# Spectre-SCH_SH2__rev.net
KiCad netlist of a schematic drawn in Altium Designer
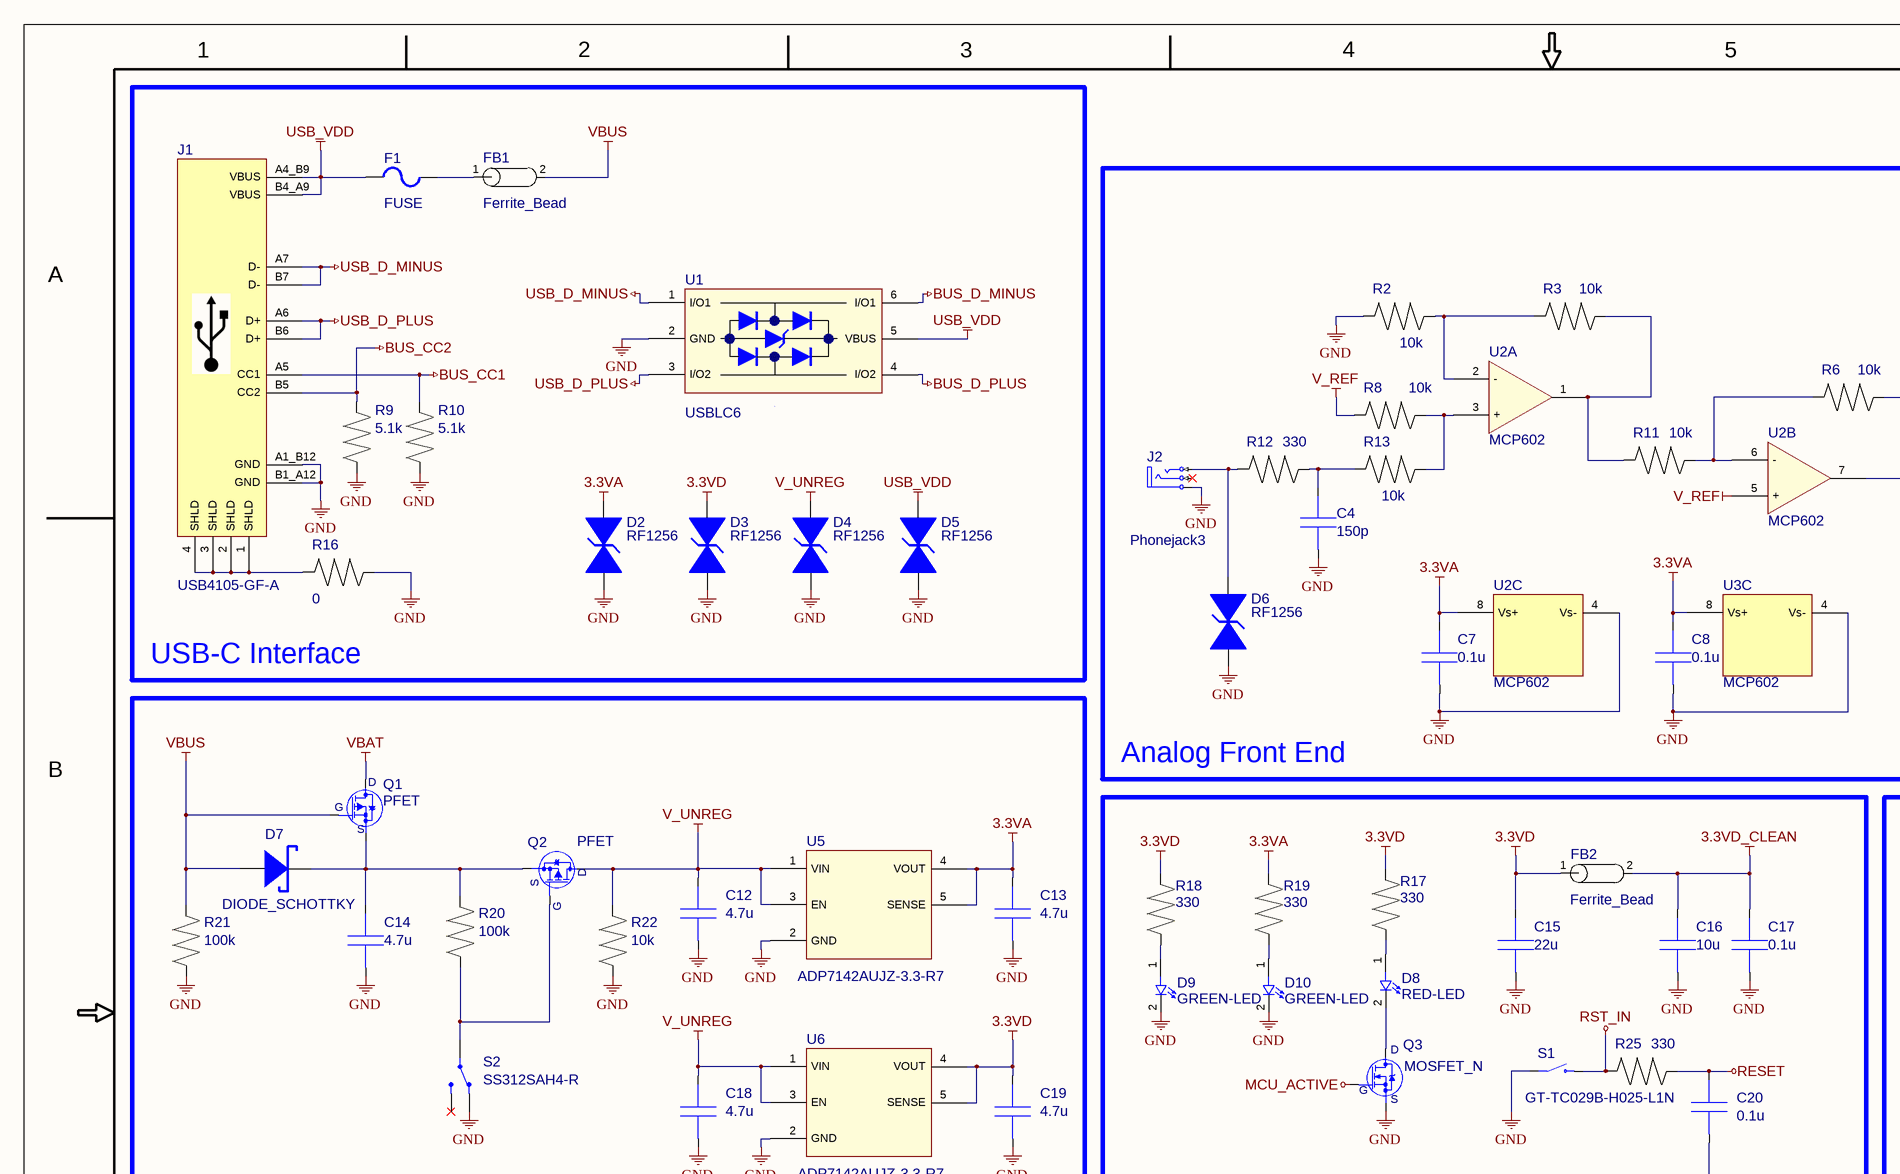
[diagram p0: Spectre-SCH_SH2_(rev).SchDoc, top left]
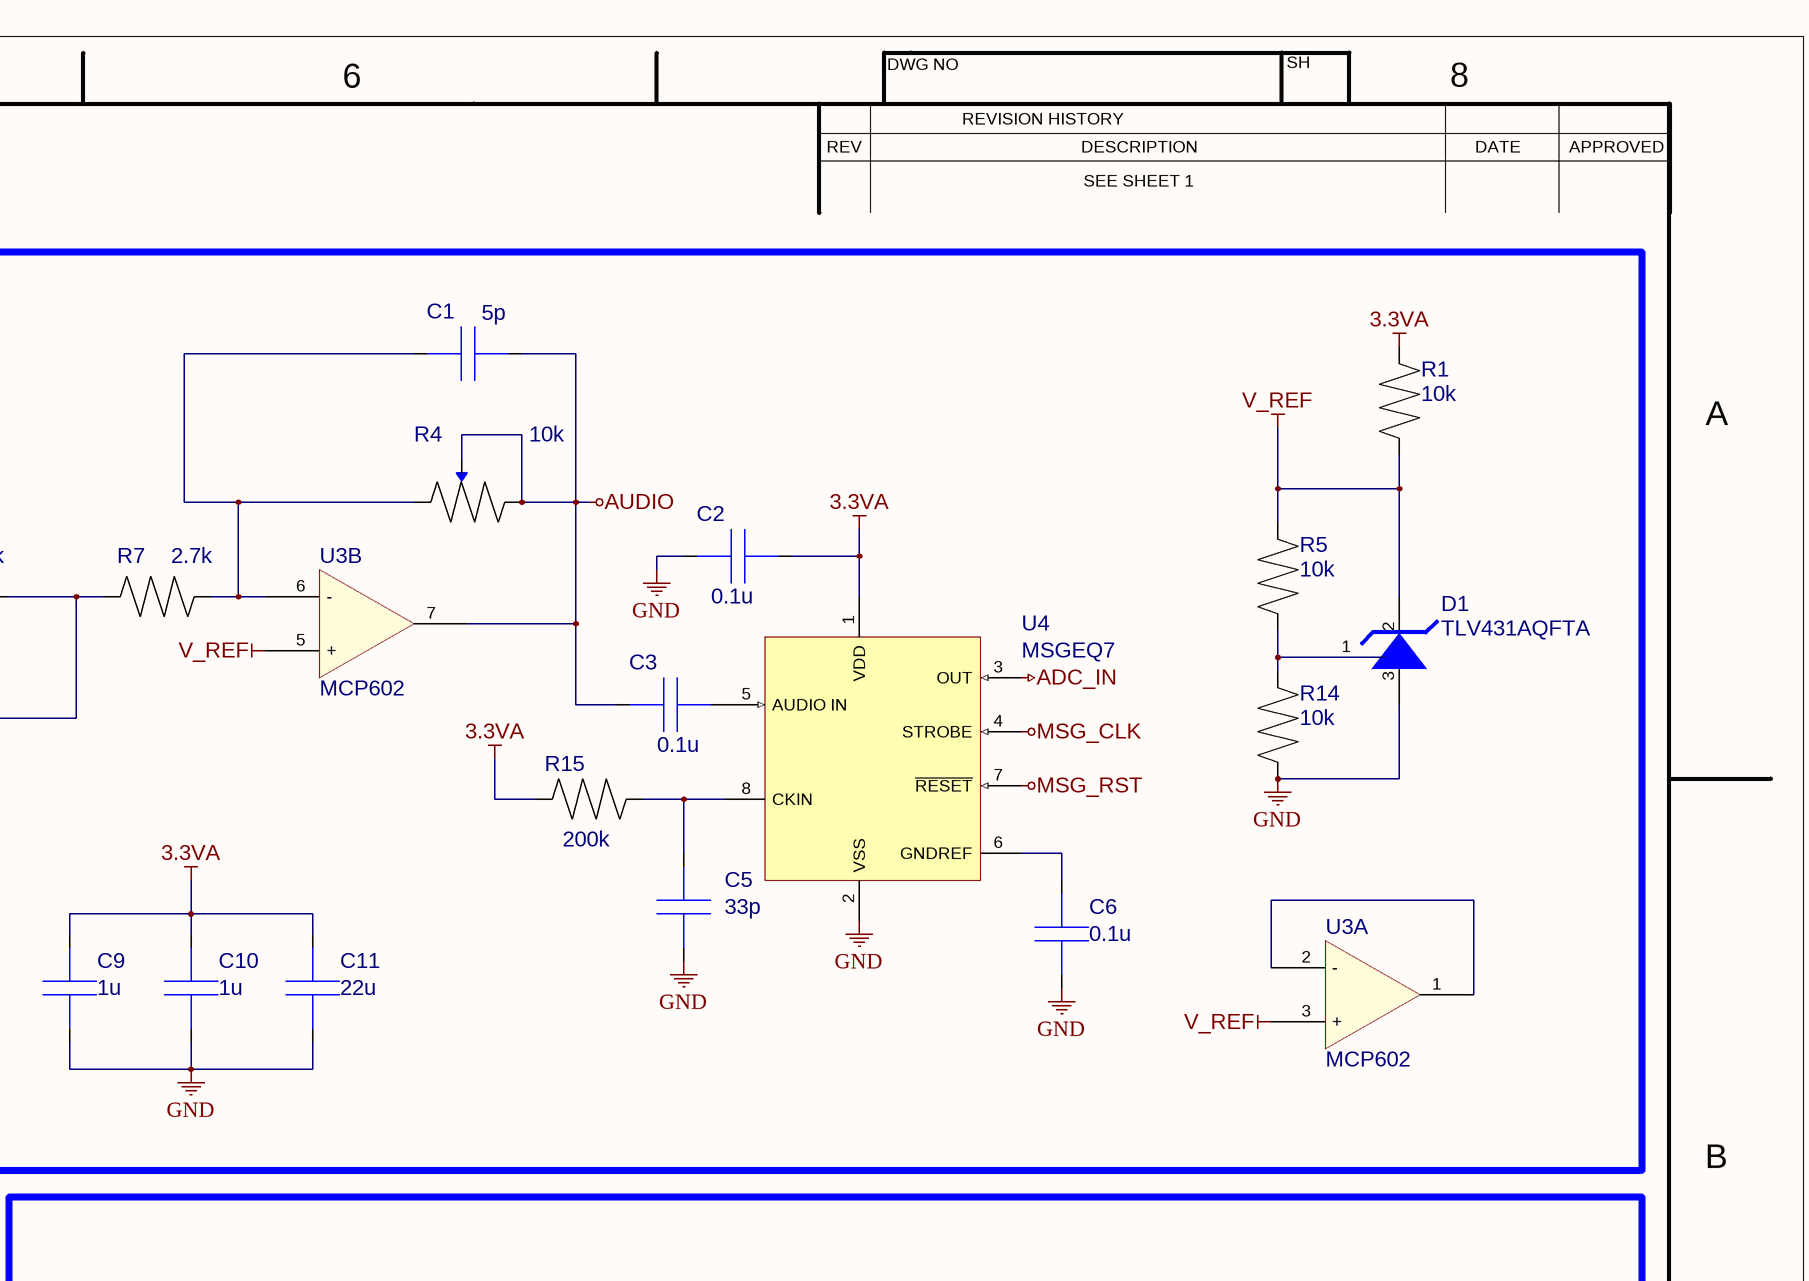
[diagram p1: Spectre-SCH_SH2_(rev).SchDoc, top right]
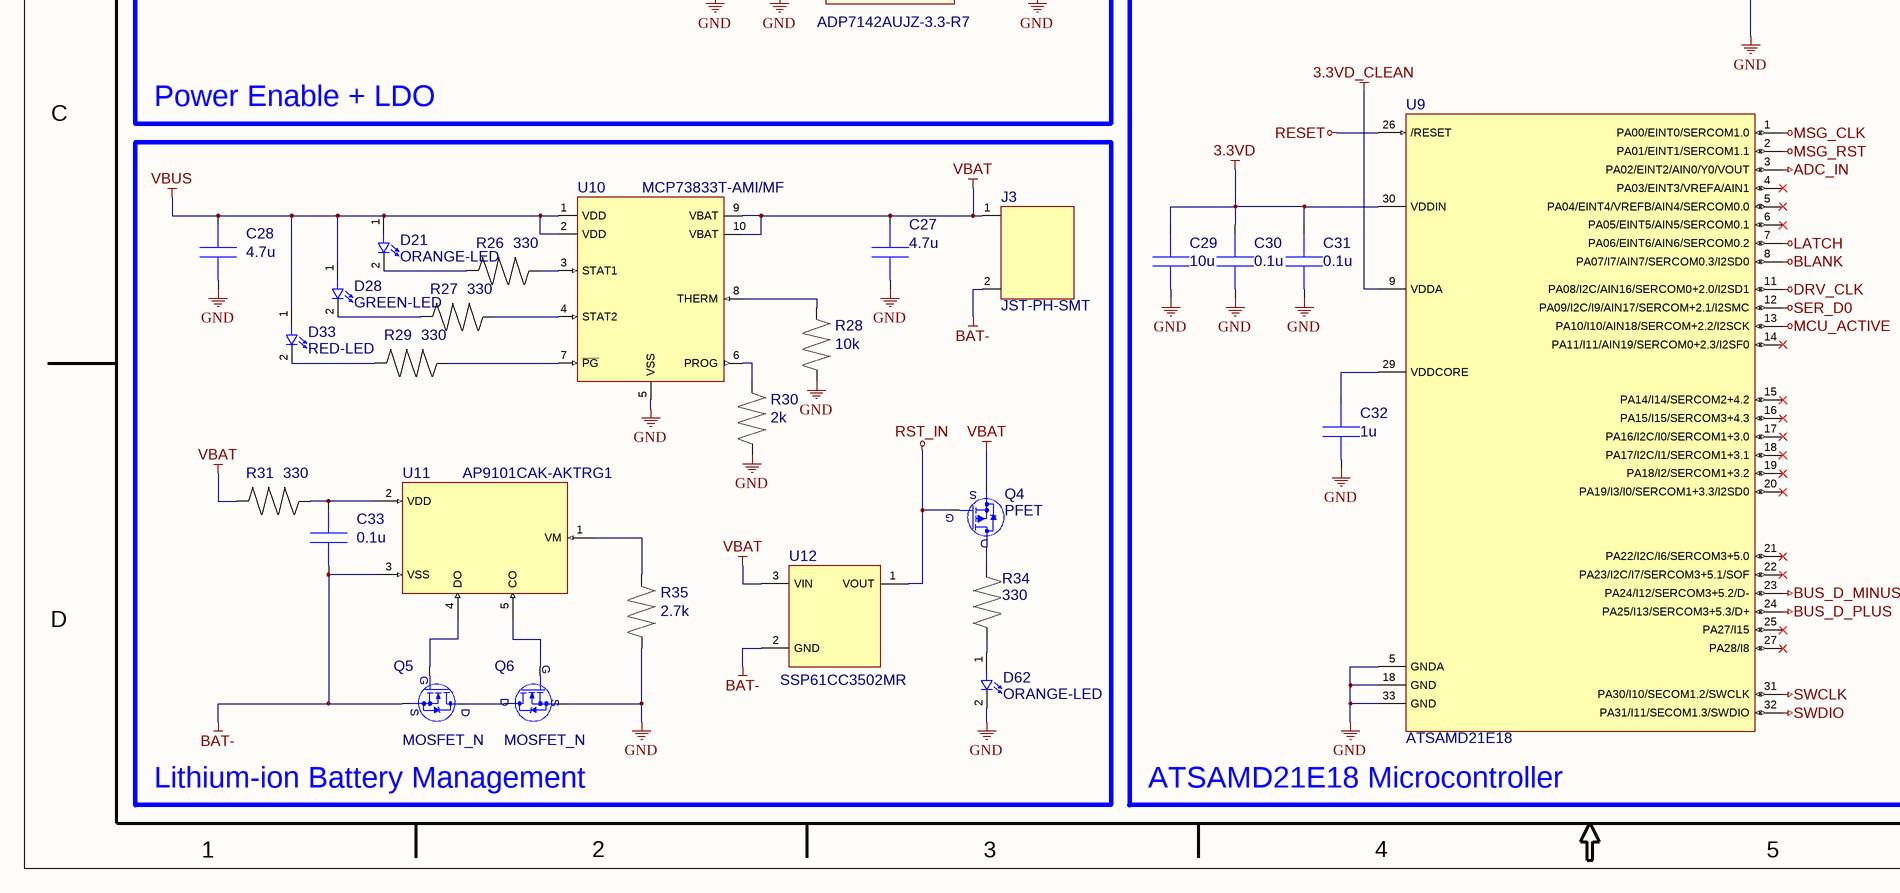
[diagram p2: Spectre-SCH_SH2_(rev).SchDoc, bottom left]
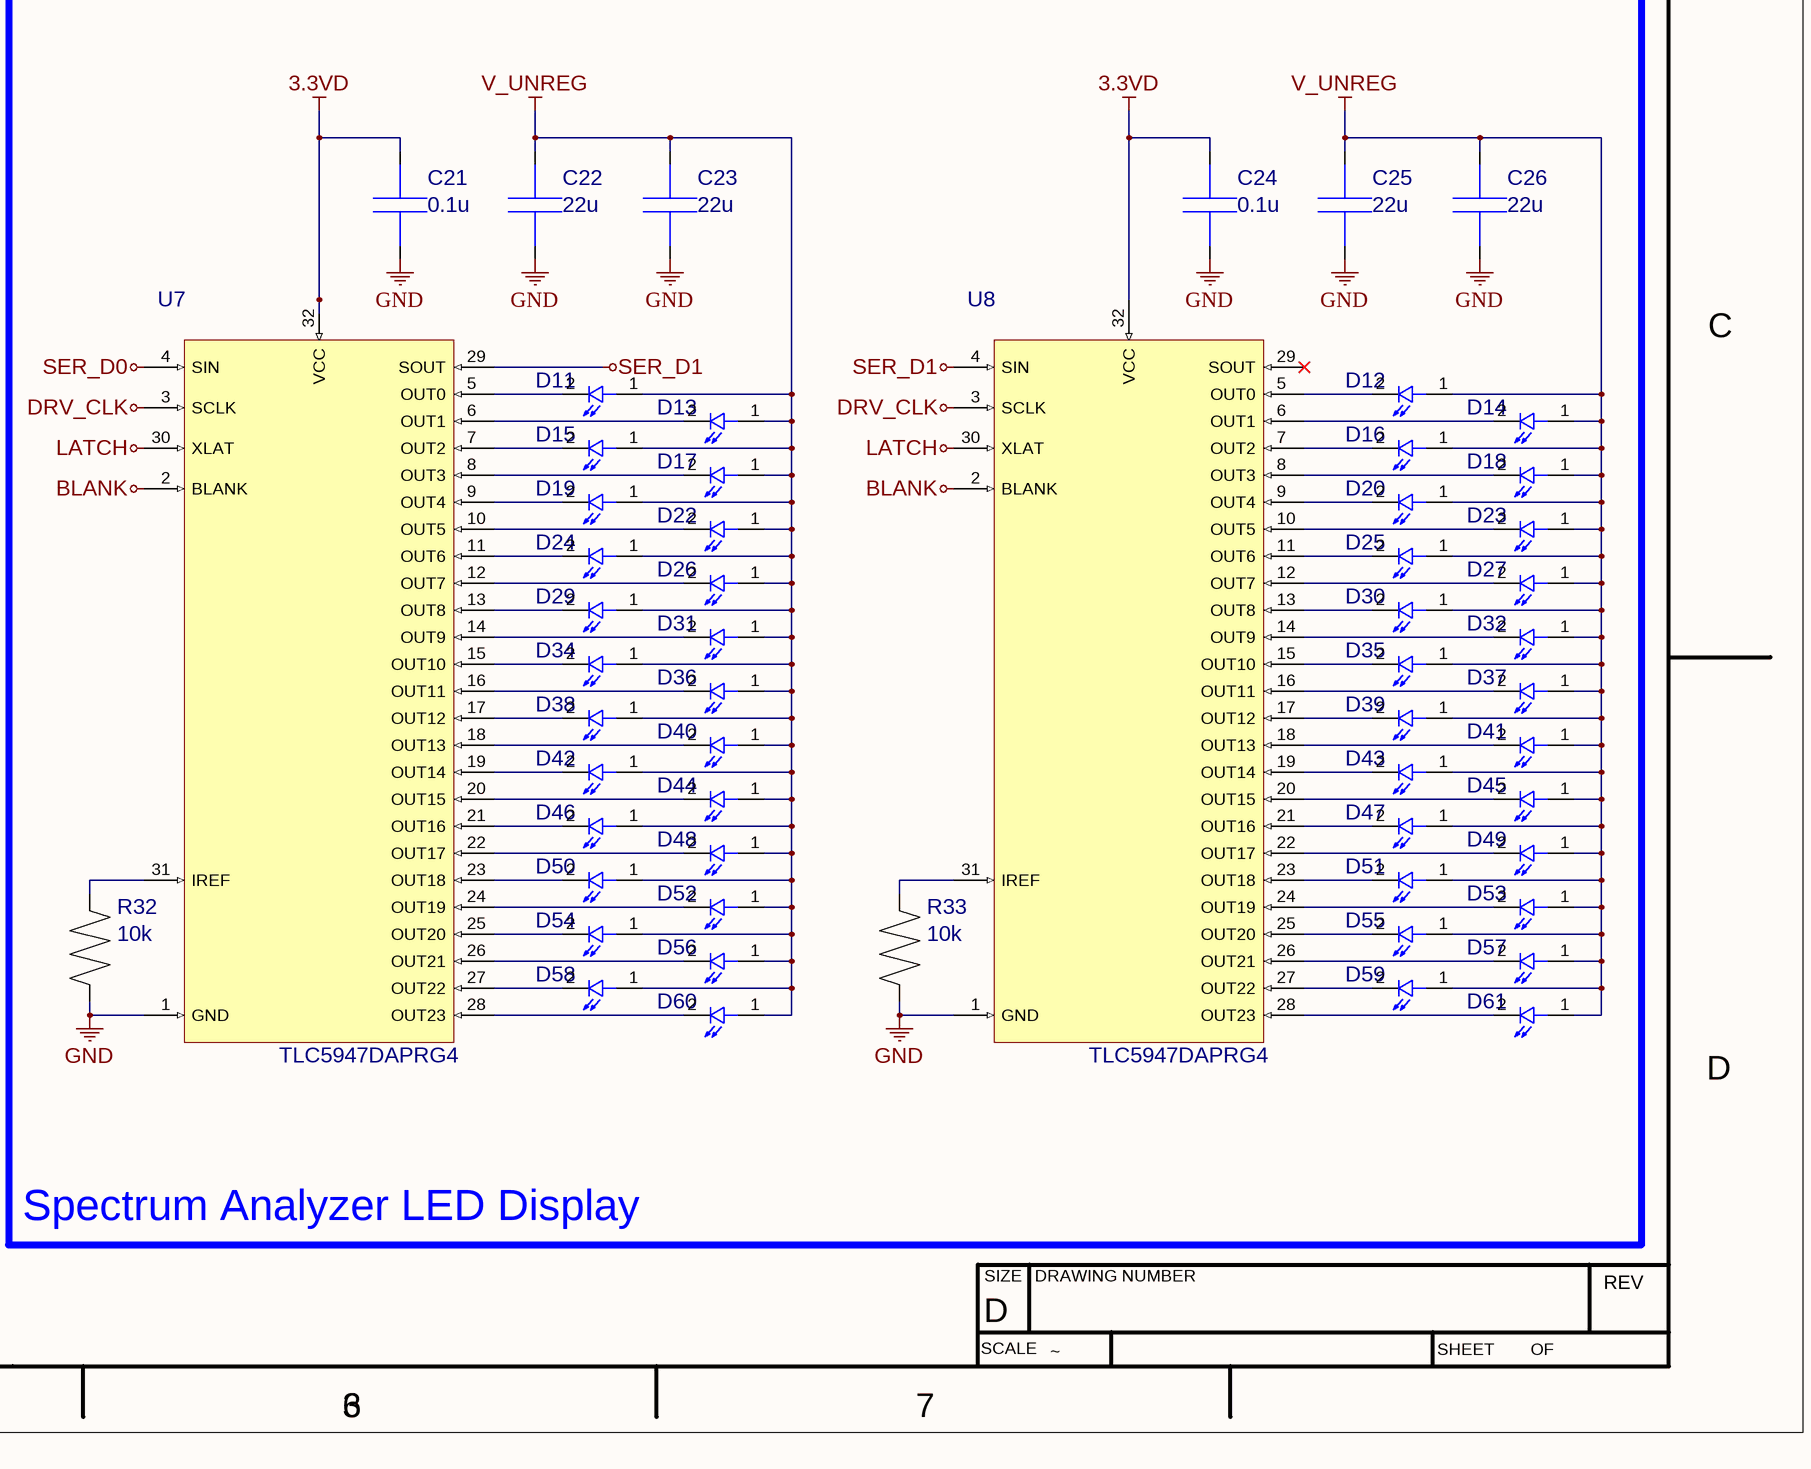
[diagram p3: Spectre-SCH_SH2_(rev).SchDoc, bottom right]

(export (version "E")
  (design (tool "Eeschema 10.0.6"))
  (components
    (comp (ref "C1") (value "5p") (footprint "0603") (libsource (lib "CAPACITORS") (part "CAP")))
    (comp (ref "C2") (value "0.1u") (footprint "0603") (libsource (lib "CAPACITORS") (part "CAP")))
    (comp (ref "C3") (value "0.1u") (footprint "0603") (libsource (lib "CAPACITORS") (part "CAP")))
    (comp (ref "C4") (value "150p") (footprint "0603") (libsource (lib "CAPACITORS") (part "CAP")))
    (comp (ref "C5") (value "33p") (footprint "0603") (libsource (lib "CAPACITORS") (part "CAP")))
    (comp (ref "C6") (value "0.1u") (footprint "0603") (libsource (lib "CAPACITORS") (part "CAP")))
    (comp (ref "C7") (value "0.1u") (footprint "0603") (libsource (lib "CAPACITORS") (part "CAP")))
    (comp (ref "C8") (value "0.1u") (footprint "0603") (libsource (lib "CAPACITORS") (part "CAP")))
    (comp (ref "C9") (value "1u") (footprint "0603") (libsource (lib "CAPACITORS") (part "CAP")))
    (comp (ref "C10") (value "1u") (footprint "0603") (libsource (lib "CAPACITORS") (part "CAP")))
    (comp (ref "C11") (value "22u") (footprint "0603") (libsource (lib "CAPACITORS") (part "CAP")))
    (comp (ref "C12") (value "4.7u") (footprint "0603") (libsource (lib "CAPACITORS") (part "CAP")))
    (comp (ref "C13") (value "4.7u") (footprint "0603") (libsource (lib "CAPACITORS") (part "CAP")))
    (comp (ref "C14") (value "4.7u") (footprint "0603") (libsource (lib "CAPACITORS") (part "CAP")))
    (comp (ref "C15") (value "22u") (footprint "0603") (libsource (lib "CAPACITORS") (part "CAP")))
    (comp (ref "C16") (value "10u") (footprint "0603") (libsource (lib "CAPACITORS") (part "CAP")))
    (comp (ref "C17") (value "0.1u") (footprint "0603") (libsource (lib "CAPACITORS") (part "CAP")))
    (comp (ref "C18") (value "4.7u") (footprint "0603") (libsource (lib "CAPACITORS") (part "CAP")))
    (comp (ref "C19") (value "4.7u") (footprint "0603") (libsource (lib "CAPACITORS") (part "CAP")))
    (comp (ref "C20") (value "0.1u") (footprint "0603") (libsource (lib "CAPACITORS") (part "CAP")))
    (comp (ref "C21") (value "0.1u") (footprint "0603") (libsource (lib "CAPACITORS") (part "CAP")))
    (comp (ref "C22") (value "22u") (footprint "0603") (libsource (lib "CAPACITORS") (part "CAP")))
    (comp (ref "C23") (value "22u") (footprint "0603") (libsource (lib "CAPACITORS") (part "CAP")))
    (comp (ref "C24") (value "0.1u") (footprint "0603") (libsource (lib "CAPACITORS") (part "CAP")))
    (comp (ref "C25") (value "22u") (footprint "0603") (libsource (lib "CAPACITORS") (part "CAP")))
    (comp (ref "C26") (value "22u") (footprint "0603") (libsource (lib "CAPACITORS") (part "CAP")))
    (comp (ref "C27") (value "4.7u") (footprint "0603") (libsource (lib "CAPACITORS") (part "CAP")))
    (comp (ref "C28") (value "4.7u") (footprint "0603") (libsource (lib "CAPACITORS") (part "CAP")))
    (comp (ref "C29") (value "10u") (footprint "0603") (libsource (lib "CAPACITORS") (part "CAP")))
    (comp (ref "C30") (value "0.1u") (footprint "0603") (libsource (lib "CAPACITORS") (part "CAP")))
    (comp (ref "C31") (value "0.1u") (footprint "0603") (libsource (lib "CAPACITORS") (part "CAP")))
    (comp (ref "C32") (value "1u") (footprint "0603") (libsource (lib "CAPACITORS") (part "CAP")))
    (comp (ref "C33") (value "0.1u") (footprint "0603") (libsource (lib "CAPACITORS") (part "CAP")))
    (comp (ref "D1")
      (value "TLV431AQFTA")
      (footprint "SOT-23-3")
      (description "Shunt Voltage Reference IC Adjustable 1.24V 18 VV ±1% 15 mA SOT-23-3")
      (fields (field (name "MANUFACTURER") "Diodes Incorporated"))
      (libsource (lib "TLV431AQFTA") (part "TLV431AQFTA"))
    )
    (comp (ref "D2")
      (value "RF1256")
      (footprint "0603")
      (description "TVS DIODE BIDIR")
      (libsource (lib "SEMICONDUCTORS") (part "DIODE_TVS_BIDIR"))
    )
    (comp (ref "D3")
      (value "RF1256")
      (footprint "0603")
      (description "TVS DIODE BIDIR")
      (libsource (lib "SEMICONDUCTORS") (part "DIODE_TVS_BIDIR"))
    )
    (comp (ref "D4")
      (value "RF1256")
      (footprint "0603")
      (description "TVS DIODE BIDIR")
      (libsource (lib "SEMICONDUCTORS") (part "DIODE_TVS_BIDIR"))
    )
    (comp (ref "D5")
      (value "RF1256")
      (footprint "0603")
      (description "TVS DIODE BIDIR")
      (libsource (lib "SEMICONDUCTORS") (part "DIODE_TVS_BIDIR"))
    )
    (comp (ref "D6")
      (value "RF1256")
      (footprint "0603")
      (description "TVS DIODE BIDIR")
      (libsource (lib "SEMICONDUCTORS") (part "DIODE_TVS_BIDIR"))
    )
    (comp (ref "D7")
      (value "DIODE_SCHOTTKY")
      (footprint "SMA")
      (description "DIODE SCHOTTKY")
      (libsource (lib "SEMICONDUCTORS") (part "DIODE_SCHOTTKY"))
    )
    (comp (ref "D8") (value "RED-LED") (footprint "0603 LED") (libsource (lib "SMT-LED") (part "SMT-LED")))
    (comp (ref "D9") (value "GREEN-LED") (footprint "0603 LED") (libsource (lib "SMT-LED") (part "SMT-LED")))
    (comp (ref "D10") (value "GREEN-LED") (footprint "0603 LED") (libsource (lib "SMT-LED") (part "SMT-LED")))
    (comp (ref "D11") (value "RED-LED") (footprint "0603 LED") (libsource (lib "SMT-LED") (part "SMT-LED")))
    (comp (ref "D12") (value "RED-LED") (footprint "0603 LED") (libsource (lib "SMT-LED") (part "SMT-LED")))
    (comp (ref "D13")
      (value "ORANGE-LED")
      (footprint "0603 LED")
      (libsource (lib "SMT-LED") (part "SMT-LED"))
    )
    (comp (ref "D14")
      (value "ORANGE-LED")
      (footprint "0603 LED")
      (libsource (lib "SMT-LED") (part "SMT-LED"))
    )
    (comp (ref "D15")
      (value "YELLOW-LED")
      (footprint "0603 LED")
      (libsource (lib "SMT-LED") (part "SMT-LED"))
    )
    (comp (ref "D16")
      (value "YELLOW-LED")
      (footprint "0603 LED")
      (libsource (lib "SMT-LED") (part "SMT-LED"))
    )
    (comp (ref "D17")
      (value "YELLOW-LED")
      (footprint "0603 LED")
      (libsource (lib "SMT-LED") (part "SMT-LED"))
    )
    (comp (ref "D18")
      (value "YELLOW-LED")
      (footprint "0603 LED")
      (libsource (lib "SMT-LED") (part "SMT-LED"))
    )
    (comp (ref "D19") (value "GREEN-LED") (footprint "0603 LED") (libsource (lib "SMT-LED") (part "SMT-LED")))
    (comp (ref "D20") (value "GREEN-LED") (footprint "0603 LED") (libsource (lib "SMT-LED") (part "SMT-LED")))
    (comp (ref "D21")
      (value "ORANGE-LED")
      (footprint "0603 LED")
      (libsource (lib "SMT-LED") (part "SMT-LED"))
    )
    (comp (ref "D22") (value "GREEN-LED") (footprint "0603 LED") (libsource (lib "SMT-LED") (part "SMT-LED")))
    (comp (ref "D23") (value "GREEN-LED") (footprint "0603 LED") (libsource (lib "SMT-LED") (part "SMT-LED")))
    (comp (ref "D24") (value "RED-LED") (footprint "0603 LED") (libsource (lib "SMT-LED") (part "SMT-LED")))
    (comp (ref "D25") (value "RED-LED") (footprint "0603 LED") (libsource (lib "SMT-LED") (part "SMT-LED")))
    (comp (ref "D26")
      (value "ORANGE-LED")
      (footprint "0603 LED")
      (libsource (lib "SMT-LED") (part "SMT-LED"))
    )
    (comp (ref "D27")
      (value "ORANGE-LED")
      (footprint "0603 LED")
      (libsource (lib "SMT-LED") (part "SMT-LED"))
    )
    (comp (ref "D28") (value "GREEN-LED") (footprint "0603 LED") (libsource (lib "SMT-LED") (part "SMT-LED")))
    (comp (ref "D29")
      (value "YELLOW-LED")
      (footprint "0603 LED")
      (libsource (lib "SMT-LED") (part "SMT-LED"))
    )
    (comp (ref "D30")
      (value "YELLOW-LED")
      (footprint "0603 LED")
      (libsource (lib "SMT-LED") (part "SMT-LED"))
    )
    (comp (ref "D31")
      (value "YELLOW-LED")
      (footprint "0603 LED")
      (libsource (lib "SMT-LED") (part "SMT-LED"))
    )
    (comp (ref "D32")
      (value "YELLOW-LED")
      (footprint "0603 LED")
      (libsource (lib "SMT-LED") (part "SMT-LED"))
    )
    (comp (ref "D33") (value "RED-LED") (footprint "0603 LED") (libsource (lib "SMT-LED") (part "SMT-LED")))
    (comp (ref "D34") (value "GREEN-LED") (footprint "0603 LED") (libsource (lib "SMT-LED") (part "SMT-LED")))
    (comp (ref "D35") (value "GREEN-LED") (footprint "0603 LED") (libsource (lib "SMT-LED") (part "SMT-LED")))
    (comp (ref "D36") (value "GREEN-LED") (footprint "0603 LED") (libsource (lib "SMT-LED") (part "SMT-LED")))
    (comp (ref "D37") (value "GREEN-LED") (footprint "0603 LED") (libsource (lib "SMT-LED") (part "SMT-LED")))
    (comp (ref "D38") (value "GREEN-LED") (footprint "0603 LED") (libsource (lib "SMT-LED") (part "SMT-LED")))
    (comp (ref "D39") (value "RED-LED") (footprint "0603 LED") (libsource (lib "SMT-LED") (part "SMT-LED")))
    (comp (ref "D40") (value "GREEN-LED") (footprint "0603 LED") (libsource (lib "SMT-LED") (part "SMT-LED")))
    (comp (ref "D41")
      (value "ORANGE-LED")
      (footprint "0603 LED")
      (libsource (lib "SMT-LED") (part "SMT-LED"))
    )
    (comp (ref "D42")
      (value "YELLOW-LED")
      (footprint "0603 LED")
      (libsource (lib "SMT-LED") (part "SMT-LED"))
    )
    (comp (ref "D43")
      (value "YELLOW-LED")
      (footprint "0603 LED")
      (libsource (lib "SMT-LED") (part "SMT-LED"))
    )
    (comp (ref "D44")
      (value "YELLOW-LED")
      (footprint "0603 LED")
      (libsource (lib "SMT-LED") (part "SMT-LED"))
    )
    (comp (ref "D45")
      (value "YELLOW-LED")
      (footprint "0603 LED")
      (libsource (lib "SMT-LED") (part "SMT-LED"))
    )
    (comp (ref "D46")
      (value "ORANGE-LED")
      (footprint "0603 LED")
      (libsource (lib "SMT-LED") (part "SMT-LED"))
    )
    (comp (ref "D47") (value "GREEN-LED") (footprint "0603 LED") (libsource (lib "SMT-LED") (part "SMT-LED")))
    (comp (ref "D48") (value "RED-LED") (footprint "0603 LED") (libsource (lib "SMT-LED") (part "SMT-LED")))
    (comp (ref "D49") (value "GREEN-LED") (footprint "0603 LED") (libsource (lib "SMT-LED") (part "SMT-LED")))
    (comp (ref "D50") (value "GREEN-LED") (footprint "0603 LED") (libsource (lib "SMT-LED") (part "SMT-LED")))
    (comp (ref "D51") (value "GREEN-LED") (footprint "0603 LED") (libsource (lib "SMT-LED") (part "SMT-LED")))
    (comp (ref "D52") (value "GREEN-LED") (footprint "0603 LED") (libsource (lib "SMT-LED") (part "SMT-LED")))
    (comp (ref "D53") (value "GREEN-LED") (footprint "0603 LED") (libsource (lib "SMT-LED") (part "SMT-LED")))
    (comp (ref "D54")
      (value "YELLOW-LED")
      (footprint "0603 LED")
      (libsource (lib "SMT-LED") (part "SMT-LED"))
    )
    (comp (ref "D55")
      (value "YELLOW-LED")
      (footprint "0603 LED")
      (libsource (lib "SMT-LED") (part "SMT-LED"))
    )
    (comp (ref "D56") (value "RED-LED") (footprint "0603 LED") (libsource (lib "SMT-LED") (part "SMT-LED")))
    (comp (ref "D57")
      (value "YELLOW-LED")
      (footprint "0603 LED")
      (libsource (lib "SMT-LED") (part "SMT-LED"))
    )
    (comp (ref "D58")
      (value "ORANGE-LED")
      (footprint "0603 LED")
      (libsource (lib "SMT-LED") (part "SMT-LED"))
    )
    (comp (ref "D59")
      (value "ORANGE-LED")
      (footprint "0603 LED")
      (libsource (lib "SMT-LED") (part "SMT-LED"))
    )
    (comp (ref "D60")
      (value "YELLOW-LED")
      (footprint "0603 LED")
      (libsource (lib "SMT-LED") (part "SMT-LED"))
    )
    (comp (ref "D61") (value "RED-LED") (footprint "0603 LED") (libsource (lib "SMT-LED") (part "SMT-LED")))
    (comp (ref "D62")
      (value "ORANGE-LED")
      (footprint "0603 LED")
      (libsource (lib "SMT-LED") (part "SMT-LED"))
    )
    (comp (ref "F1") (value "FUSE") (footprint "1206") (libsource (lib "Power") (part "FUSE")))
    (comp (ref "FB1")
      (value "Ferrite_Bead")
      (footprint "0603")
      (description "Ferrite Bead")
      (libsource (lib "Ferrite_Beads") (part "Ferrite_Bead"))
    )
    (comp (ref "FB2")
      (value "Ferrite_Bead")
      (footprint "0603")
      (description "Ferrite Bead")
      (libsource (lib "Ferrite_Beads") (part "Ferrite_Bead"))
    )
    (comp (ref "J1")
      (value "USB4105-GF-A")
      (footprint "USB4105-GF-A")
      (fields (field (name "MANUFACTURER") "GCT"))
      (libsource (lib "USB4105-GF-A") (part "USB4105-GF-A"))
    )
    (comp (ref "J2")
      (value "Phonejack3")
      (footprint "STX-3500-3NTR")
      (description "Jack Socket, 1/4\" [6.5mm], Thru-Hole, Vertical, 3-Conductor Open Circuit (Non-Normalling)")
      (fields (field (name "PUBLISHER") "Altium Limited"))
      (libsource (lib "Miscellaneous Connectors") (part "Phonejack3"))
    )
    (comp (ref "J3")
      (value "JST-PH-SMT")
      (footprint "JST-PH-SMT")
      (libsource (lib "JST-PH-SMT") (part "JST-PH-SMT"))
    )
    (comp (ref "Q1")
      (value "PFET")
      (footprint "TO-252-3")
      (description "MOSFET, P CH, 3-PIN")
      (libsource (lib "") (part "MOSFET_P_2"))
    )
    (comp (ref "Q2")
      (value "PFET")
      (footprint "TO-252-3")
      (description "MOSFET, P CH, 3-PIN")
      (libsource (lib "SEMICONDUCTORS") (part "MOSFET_P"))
    )
    (comp (ref "Q3")
      (value "MOSFET_N")
      (footprint "SOT-23")
      (description "MOSFET, N CH, 3-PIN")
      (libsource (lib "") (part "MOSFET_N_1"))
    )
    (comp (ref "Q4")
      (value "PFET")
      (footprint "SOT-23")
      (description "MOSFET, P CH, 3-PIN")
      (libsource (lib "") (part "MOSFET_P_1"))
    )
    (comp (ref "Q5")
      (value "MOSFET_N")
      (footprint "SOT-23")
      (description "MOSFET, N CH, 3-PIN")
      (libsource (lib "") (part "MOSFET_N_2"))
    )
    (comp (ref "Q6")
      (value "MOSFET_N")
      (footprint "SOT-23")
      (description "MOSFET, N CH, 3-PIN")
      (libsource (lib "SEMICONDUCTORS") (part "MOSFET_N"))
    )
    (comp (ref "R1")
      (value "10k")
      (footprint "0603")
      (description "RESISTOR")
      (libsource (lib "RESISTORS") (part "RES"))
    )
    (comp (ref "R2")
      (value "10k")
      (footprint "0603")
      (description "RESISTOR")
      (libsource (lib "RESISTORS") (part "RES"))
    )
    (comp (ref "R3")
      (value "10k")
      (footprint "0603")
      (description "RESISTOR")
      (libsource (lib "RESISTORS") (part "RES"))
    )
    (comp (ref "R4")
      (value "10k")
      (footprint "ALPS 9mm")
      (description "10 kOhms - PC Pin Through Hole Trimmer Potentiometer - Turn Top Adjustment")
      (fields (field (name "MANUFACTURER") "Adafruit Industries LLC") (field (name "PART NUMBER") "356"))
      (libsource (lib "ADAFRUIT-10K") (part "Adafruit 356"))
    )
    (comp (ref "R5")
      (value "10k")
      (footprint "0603")
      (description "RESISTOR")
      (libsource (lib "RESISTORS") (part "RES"))
    )
    (comp (ref "R6")
      (value "10k")
      (footprint "0603")
      (description "RESISTOR")
      (libsource (lib "RESISTORS") (part "RES"))
    )
    (comp (ref "R7")
      (value "2.7k")
      (footprint "0603")
      (description "RESISTOR")
      (libsource (lib "RESISTORS") (part "RES"))
    )
    (comp (ref "R8")
      (value "10k")
      (footprint "0603")
      (description "RESISTOR")
      (libsource (lib "RESISTORS") (part "RES"))
    )
    (comp (ref "R9")
      (value "5.1k")
      (footprint "0603")
      (description "RESISTOR")
      (libsource (lib "RESISTORS") (part "RES"))
    )
    (comp (ref "R10")
      (value "5.1k")
      (footprint "0603")
      (description "RESISTOR")
      (libsource (lib "RESISTORS") (part "RES"))
    )
    (comp (ref "R11")
      (value "10k")
      (footprint "0603")
      (description "RESISTOR")
      (libsource (lib "RESISTORS") (part "RES"))
    )
    (comp (ref "R12")
      (value "330")
      (footprint "0603")
      (description "RESISTOR")
      (libsource (lib "RESISTORS") (part "RES"))
    )
    (comp (ref "R13")
      (value "10k")
      (footprint "0603")
      (description "RESISTOR")
      (libsource (lib "RESISTORS") (part "RES"))
    )
    (comp (ref "R14")
      (value "10k")
      (footprint "0603")
      (description "RESISTOR")
      (libsource (lib "RESISTORS") (part "RES"))
    )
    (comp (ref "R15")
      (value "200k")
      (footprint "0603")
      (description "RESISTOR")
      (libsource (lib "RESISTORS") (part "RES"))
    )
    (comp (ref "R16")
      (value "0")
      (footprint "0603")
      (description "RESISTOR")
      (libsource (lib "RESISTORS") (part "RES"))
    )
    (comp (ref "R17")
      (value "330")
      (footprint "0603")
      (description "RESISTOR")
      (libsource (lib "RESISTORS") (part "RES"))
    )
    (comp (ref "R18")
      (value "330")
      (footprint "0603")
      (description "RESISTOR")
      (libsource (lib "RESISTORS") (part "RES"))
    )
    (comp (ref "R19")
      (value "330")
      (footprint "0603")
      (description "RESISTOR")
      (libsource (lib "RESISTORS") (part "RES"))
    )
    (comp (ref "R20")
      (value "100k")
      (footprint "0603")
      (description "RESISTOR")
      (libsource (lib "RESISTORS") (part "RES"))
    )
    (comp (ref "R21")
      (value "100k")
      (footprint "0603")
      (description "RESISTOR")
      (libsource (lib "RESISTORS") (part "RES"))
    )
    (comp (ref "R22")
      (value "10k")
      (footprint "0603")
      (description "RESISTOR")
      (libsource (lib "RESISTORS") (part "RES"))
    )
    (comp (ref "R25")
      (value "330")
      (footprint "0603")
      (description "RESISTOR")
      (libsource (lib "RESISTORS") (part "RES"))
    )
    (comp (ref "R26")
      (value "330")
      (footprint "0603")
      (description "RESISTOR")
      (libsource (lib "RESISTORS") (part "RES"))
    )
    (comp (ref "R27")
      (value "330")
      (footprint "0603")
      (description "RESISTOR")
      (libsource (lib "RESISTORS") (part "RES"))
    )
    (comp (ref "R28")
      (value "10k")
      (footprint "0603")
      (description "RESISTOR")
      (libsource (lib "RESISTORS") (part "RES"))
    )
    (comp (ref "R29")
      (value "330")
      (footprint "0603")
      (description "RESISTOR")
      (libsource (lib "RESISTORS") (part "RES"))
    )
    (comp (ref "R30")
      (value "2k")
      (footprint "0603")
      (description "RESISTOR")
      (libsource (lib "RESISTORS") (part "RES"))
    )
    (comp (ref "R31")
      (value "330")
      (footprint "0603")
      (description "RESISTOR")
      (libsource (lib "RESISTORS") (part "RES"))
    )
    (comp (ref "R32")
      (value "10k")
      (footprint "0603")
      (description "RESISTOR")
      (libsource (lib "RESISTORS") (part "RES"))
    )
    (comp (ref "R33")
      (value "10k")
      (footprint "0603")
      (description "RESISTOR")
      (libsource (lib "RESISTORS") (part "RES"))
    )
    (comp (ref "R34")
      (value "330")
      (footprint "0603")
      (description "RESISTOR")
      (libsource (lib "RESISTORS") (part "RES"))
    )
    (comp (ref "R35")
      (value "2.7k")
      (footprint "0603")
      (description "RESISTOR")
      (libsource (lib "RESISTORS") (part "RES"))
    )
    (comp (ref "S1")
      (value "GT-TC029B-H025-L1N")
      (footprint "GT-TC029B-H025-L1N")
      (libsource (lib "GT-TC029B-H025-L1N") (part "GT-TC029B-H025-L1N"))
    )
    (comp (ref "S2")
      (value "SS312SAH4-R")
      (footprint "SW_SS312SAH4-R")
      (description "Slide Switch SPDT Surface Mount, Right Angle")
      (fields (field (name "MANUFACTURER") "NKK Switches"))
      (libsource (lib "SS312SAH4-R") (part "SS312SAH4-R"))
    )
    (comp (ref "U1")
      (value "USBLC6")
      (footprint "SOT-23-6_N")
      (description "IC ESD PROTECTION LO CAP SOT23-6")
      (fields (field (name "PART NUMBER") "USBLC6-2SC6") (field (name "MANUFACTURER") "STMicroelectronics"))
      (libsource (lib "SEMICONDUCTORS") (part "USBLC6-2SC6"))
    )
    (comp (ref "U2")
      (value "MCP602")
      (footprint "MSOP-8")
      (description "IC OPAMP VIDEO DUAL 8MSOP")
      (fields (field (name "PART NUMBER") "AD8072ARMZ") (field (name "MANUFACTURER") "Analog Devices Inc."))
      (libsource (lib "Op_Amps") (part "AD8072"))
    )
    (comp (ref "U3")
      (value "MCP602")
      (footprint "MSOP-8")
      (description "IC OPAMP VIDEO DUAL 8MSOP")
      (fields (field (name "PART NUMBER") "AD8072ARMZ") (field (name "MANUFACTURER") "Analog Devices Inc."))
      (libsource (lib "Op_Amps") (part "AD8072"))
    )
    (comp (ref "U4") (value "MSGEQ7") (footprint "MSGEQ7") (libsource (lib "MSGEQ7") (part "MSGEQ7")))
    (comp (ref "U5")
      (value "ADP7142AUJZ-3.3-R7")
      (footprint "TSOT-23-5")
      (libsource (lib "ADP7142AUJZ-3.3-R7") (part "ADP7142AUJZ-3.3-R7"))
    )
    (comp (ref "U6")
      (value "ADP7142AUJZ-3.3-R7")
      (footprint "TSOT-23-5")
      (libsource (lib "ADP7142AUJZ-3.3-R7") (part "ADP7142AUJZ-3.3-R7"))
    )
    (comp (ref "U7")
      (value "TLC5947DAPRG4")
      (footprint "*SOP65P810X120-32N")
      (libsource (lib "TLC5947DAPRG4") (part "TLC5947DAPRG4"))
    )
    (comp (ref "U8")
      (value "TLC5947DAPRG4")
      (footprint "*SOP65P810X120-32N")
      (libsource (lib "TLC5947DAPRG4") (part "TLC5947DAPRG4"))
    )
    (comp (ref "U9")
      (value "ATSAMD21E18")
      (footprint "QFN-32 Handsolder")
      (libsource (lib "ATSAMD21E18") (part "ATSAMD21E18"))
    )
    (comp (ref "U10")
      (value "MCP73833T-AMI/MF")
      (footprint "MSOP-10")
      (description "Charger IC Lithium Ion/Polymer 10-DFN _3x3_")
      (fields (field (name "MF") "Microchip"))
      (libsource (lib "MCP73833") (part "MCP73833T-AMI/MF"))
    )
    (comp (ref "U11")
      (value "AP9101CAK-AKTRG1")
      (footprint "SOT-23-5")
      (libsource (lib "AP9101CAK-AKTRG1") (part "AP9101CAK-AKTRG1"))
    )
    (comp (ref "U12")
      (value "SSP61CC3502MR")
      (footprint "SOT-23-3")
      (libsource (lib "SSP61C") (part "SSP61C"))
    )
  )
  (nets
    (net (code "1") (name "3.3VA") (class "Default")
      (node (ref "C10") (pin "2") (pinfunction "2_2") (pintype "passive"))
      (node (ref "C11") (pin "2") (pinfunction "2_2") (pintype "passive"))
      (node (ref "C13") (pin "2") (pinfunction "2_2") (pintype "passive"))
      (node (ref "C2") (pin "1") (pinfunction "1_1") (pintype "passive"))
      (node (ref "C7") (pin "2") (pinfunction "2_2") (pintype "passive"))
      (node (ref "C8") (pin "2") (pinfunction "2_2") (pintype "passive"))
      (node (ref "C9") (pin "2") (pinfunction "2_2") (pintype "passive"))
      (node (ref "D2") (pin "2") (pinfunction "2_2") (pintype "passive"))
      (node (ref "R1") (pin "1") (pinfunction "1_1") (pintype "passive"))
      (node (ref "R15") (pin "2") (pinfunction "2_2") (pintype "passive"))
      (node (ref "R19") (pin "2") (pinfunction "2_2") (pintype "passive"))
      (node (ref "U2") (pin "8") (pinfunction "Vs+_8") (pintype "power_in"))
      (node (ref "U3") (pin "8") (pinfunction "Vs+_8") (pintype "power_in"))
      (node (ref "U4") (pin "1") (pinfunction "VDD_1") (pintype "power_in"))
      (node (ref "U5") (pin "4") (pinfunction "VOUT_4") (pintype "passive"))
      (node (ref "U5") (pin "5") (pinfunction "SENSE_5") (pintype "passive"))
    )
    (net (code "2") (name "3.3VD") (class "Default")
      (node (ref "C15") (pin "2") (pinfunction "2_2") (pintype "passive"))
      (node (ref "C19") (pin "2") (pinfunction "2_2") (pintype "passive"))
      (node (ref "C21") (pin "2") (pinfunction "2_2") (pintype "passive"))
      (node (ref "C24") (pin "2") (pinfunction "2_2") (pintype "passive"))
      (node (ref "C29") (pin "2") (pinfunction "2_2") (pintype "passive"))
      (node (ref "C30") (pin "2") (pinfunction "2_2") (pintype "passive"))
      (node (ref "C31") (pin "2") (pinfunction "2_2") (pintype "passive"))
      (node (ref "D3") (pin "2") (pinfunction "2_2") (pintype "passive"))
      (node (ref "FB2") (pin "1") (pinfunction "1_1") (pintype "passive"))
      (node (ref "R17") (pin "2") (pinfunction "2_2") (pintype "passive"))
      (node (ref "R18") (pin "2") (pinfunction "2_2") (pintype "passive"))
      (node (ref "U6") (pin "4") (pinfunction "VOUT_4") (pintype "passive"))
      (node (ref "U6") (pin "5") (pinfunction "SENSE_5") (pintype "passive"))
      (node (ref "U7") (pin "32") (pinfunction "VCC_32") (pintype "input"))
      (node (ref "U8") (pin "32") (pinfunction "VCC_32") (pintype "input"))
      (node (ref "U9") (pin "30") (pinfunction "VDDIN_30") (pintype "power_in"))
    )
    (net (code "3") (name "3.3VD_CLEAN") (class "Default")
      (node (ref "C16") (pin "2") (pinfunction "2_2") (pintype "passive"))
      (node (ref "C17") (pin "2") (pinfunction "2_2") (pintype "passive"))
      (node (ref "FB2") (pin "2") (pinfunction "2_2") (pintype "passive"))
      (node (ref "U9") (pin "9") (pinfunction "VDDA_9") (pintype "power_in"))
    )
    (net (code "4") (name "ADC_IN") (class "Default")
      (node (ref "U4") (pin "3") (pinfunction "OUT_3") (pintype "input"))
      (node (ref "U9") (pin "3") (pinfunction "PA02/EINT2/AIN0/Y0/VOUT_3") (pintype "bidirectional"))
    )
    (net (code "5") (name "AUDIO") (class "Default")
      (node (ref "C1") (pin "1") (pinfunction "1_1") (pintype "passive"))
      (node (ref "C3") (pin "2") (pinfunction "2_2") (pintype "passive"))
      (node (ref "R4") (pin "2") (pinfunction "2_2") (pintype "passive"))
      (node (ref "R4") (pin "3") (pinfunction "3_3") (pintype "passive"))
      (node (ref "U3") (pin "7") (pinfunction "OUT_7") (pintype "passive"))
    )
    (net (code "6") (name "BAT-") (class "Default")
      (node (ref "C33") (pin "1") (pinfunction "1_1") (pintype "passive"))
      (node (ref "J3") (pin "2") (pinfunction "2_2") (pintype "passive"))
      (node (ref "Q5") (pin "3") (pinfunction "S_3") (pintype "passive"))
      (node (ref "U11") (pin "3") (pinfunction "VSS_3") (pintype "input"))
      (node (ref "U12") (pin "2") (pinfunction "GND_2") (pintype "power_in"))
    )
    (net (code "7") (name "BLANK") (class "Default")
      (node (ref "U7") (pin "2") (pinfunction "BLANK_2") (pintype "input"))
      (node (ref "U8") (pin "2") (pinfunction "BLANK_2") (pintype "input"))
      (node (ref "U9") (pin "8") (pinfunction "PA07/I7/AIN7/SERCOM0.3/I2SD0_8") (pintype "bidirectional"))
    )
    (net (code "8") (name "BUS_CC1") (class "Default")
      (node (ref "J1") (pin "A5") (pinfunction "CC1_A5") (pintype "passive"))
      (node (ref "R10") (pin "2") (pinfunction "2_2") (pintype "passive"))
    )
    (net (code "9") (name "BUS_CC2") (class "Default")
      (node (ref "J1") (pin "B5") (pinfunction "CC2_B5") (pintype "passive"))
      (node (ref "R9") (pin "2") (pinfunction "2_2") (pintype "passive"))
    )
    (net (code "10") (name "BUS_D_MINUS") (class "Default")
      (node (ref "U1") (pin "6") (pinfunction "I/O1_6") (pintype "passive"))
      (node (ref "U9") (pin "23") (pinfunction "PA24/I12/SERCOM3+5.2/D-_23") (pintype "bidirectional"))
    )
    (net (code "11") (name "BUS_D_PLUS") (class "Default")
      (node (ref "U1") (pin "4") (pinfunction "I/O2_4") (pintype "passive"))
      (node (ref "U9") (pin "24") (pinfunction "PA25/I13/SERCOM3+5.3/D+_24") (pintype "bidirectional"))
    )
    (net (code "12") (name "DRV_CLK") (class "Default")
      (node (ref "U7") (pin "3") (pinfunction "SCLK_3") (pintype "input"))
      (node (ref "U8") (pin "3") (pinfunction "SCLK_3") (pintype "input"))
      (node (ref "U9") (pin "11") (pinfunction "PA08/I2C/AIN16/SERCOM0+2.0/I2SD1_11") (pintype "bidirectional"))
    )
    (net (code "13") (name "GND") (class "Default")
      (node (ref "C10") (pin "1") (pinfunction "1_1") (pintype "passive"))
      (node (ref "C11") (pin "1") (pinfunction "1_1") (pintype "passive"))
      (node (ref "C12") (pin "1") (pinfunction "1_1") (pintype "passive"))
      (node (ref "C13") (pin "1") (pinfunction "1_1") (pintype "passive"))
      (node (ref "C14") (pin "1") (pinfunction "1_1") (pintype "passive"))
      (node (ref "C15") (pin "1") (pinfunction "1_1") (pintype "passive"))
      (node (ref "C16") (pin "1") (pinfunction "1_1") (pintype "passive"))
      (node (ref "C17") (pin "1") (pinfunction "1_1") (pintype "passive"))
      (node (ref "C18") (pin "1") (pinfunction "1_1") (pintype "passive"))
      (node (ref "C19") (pin "1") (pinfunction "1_1") (pintype "passive"))
      (node (ref "C2") (pin "2") (pinfunction "2_2") (pintype "passive"))
      (node (ref "C20") (pin "1") (pinfunction "1_1") (pintype "passive"))
      (node (ref "C21") (pin "1") (pinfunction "1_1") (pintype "passive"))
      (node (ref "C22") (pin "1") (pinfunction "1_1") (pintype "passive"))
      (node (ref "C23") (pin "1") (pinfunction "1_1") (pintype "passive"))
      (node (ref "C24") (pin "1") (pinfunction "1_1") (pintype "passive"))
      (node (ref "C25") (pin "1") (pinfunction "1_1") (pintype "passive"))
      (node (ref "C26") (pin "1") (pinfunction "1_1") (pintype "passive"))
      (node (ref "C27") (pin "1") (pinfunction "1_1") (pintype "passive"))
      (node (ref "C28") (pin "1") (pinfunction "1_1") (pintype "passive"))
      (node (ref "C29") (pin "1") (pinfunction "1_1") (pintype "passive"))
      (node (ref "C30") (pin "1") (pinfunction "1_1") (pintype "passive"))
      (node (ref "C31") (pin "1") (pinfunction "1_1") (pintype "passive"))
      (node (ref "C32") (pin "1") (pinfunction "1_1") (pintype "passive"))
      (node (ref "C4") (pin "1") (pinfunction "1_1") (pintype "passive"))
      (node (ref "C5") (pin "2") (pinfunction "2_2") (pintype "passive"))
      (node (ref "C6") (pin "2") (pinfunction "2_2") (pintype "passive"))
      (node (ref "C7") (pin "1") (pinfunction "1_1") (pintype "passive"))
      (node (ref "C8") (pin "1") (pinfunction "1_1") (pintype "passive"))
      (node (ref "C9") (pin "1") (pinfunction "1_1") (pintype "passive"))
      (node (ref "D1") (pin "3") (pinfunction "A_3") (pintype "passive"))
      (node (ref "D10") (pin "2") (pinfunction "2_2") (pintype "passive"))
      (node (ref "D2") (pin "1") (pinfunction "1_1") (pintype "passive"))
      (node (ref "D3") (pin "1") (pinfunction "1_1") (pintype "passive"))
      (node (ref "D4") (pin "1") (pinfunction "1_1") (pintype "passive"))
      (node (ref "D5") (pin "1") (pinfunction "1_1") (pintype "passive"))
      (node (ref "D6") (pin "1") (pinfunction "1_1") (pintype "passive"))
      (node (ref "D62") (pin "2") (pinfunction "2_2") (pintype "passive"))
      (node (ref "D9") (pin "2") (pinfunction "2_2") (pintype "passive"))
      (node (ref "J1") (pin "A1_B12") (pinfunction "GND_A1_B12") (pintype "passive"))
      (node (ref "J1") (pin "B1_A12") (pinfunction "GND_B1_A12") (pintype "passive"))
      (node (ref "J2") (pin "1") (pinfunction "S_1") (pintype "power_in"))
      (node (ref "Q3") (pin "3") (pinfunction "S_3") (pintype "passive"))
      (node (ref "Q6") (pin "3") (pinfunction "S_3") (pintype "passive"))
      (node (ref "R10") (pin "1") (pinfunction "1_1") (pintype "passive"))
      (node (ref "R14") (pin "2") (pinfunction "2_2") (pintype "passive"))
      (node (ref "R16") (pin "1") (pinfunction "1_1") (pintype "passive"))
      (node (ref "R2") (pin "2") (pinfunction "2_2") (pintype "passive"))
      (node (ref "R21") (pin "1") (pinfunction "1_1") (pintype "passive"))
      (node (ref "R22") (pin "1") (pinfunction "1_1") (pintype "passive"))
      (node (ref "R28") (pin "2") (pinfunction "2_2") (pintype "passive"))
      (node (ref "R30") (pin "2") (pinfunction "2_2") (pintype "passive"))
      (node (ref "R32") (pin "1") (pinfunction "1_1") (pintype "passive"))
      (node (ref "R33") (pin "1") (pinfunction "1_1") (pintype "passive"))
      (node (ref "R35") (pin "2") (pinfunction "2_2") (pintype "passive"))
      (node (ref "R9") (pin "1") (pinfunction "1_1") (pintype "passive"))
      (node (ref "S1") (pin "1") (pinfunction "1_1") (pintype "passive"))
      (node (ref "S2") (pin "1") (pinfunction "1_1") (pintype "passive"))
      (node (ref "U1") (pin "2") (pinfunction "GND_2") (pintype "passive"))
      (node (ref "U10") (pin "5") (pinfunction "VSS_5") (pintype "power_in"))
      (node (ref "U2") (pin "4") (pinfunction "Vs-_4") (pintype "power_in"))
      (node (ref "U3") (pin "4") (pinfunction "Vs-_4") (pintype "power_in"))
      (node (ref "U4") (pin "2") (pinfunction "VSS_2") (pintype "power_in"))
      (node (ref "U5") (pin "2") (pinfunction "GND_2") (pintype "passive"))
      (node (ref "U6") (pin "2") (pinfunction "GND_2") (pintype "passive"))
      (node (ref "U7") (pin "1") (pinfunction "GND_1") (pintype "input"))
      (node (ref "U8") (pin "1") (pinfunction "GND_1") (pintype "input"))
      (node (ref "U9") (pin "18") (pinfunction "GND_18") (pintype "power_in"))
      (node (ref "U9") (pin "33") (pinfunction "GND_33") (pintype "power_in"))
      (node (ref "U9") (pin "5") (pinfunction "GNDA_5") (pintype "power_in"))
    )
    (net (code "14") (name "LATCH") (class "Default")
      (node (ref "U7") (pin "30") (pinfunction "XLAT_30") (pintype "input"))
      (node (ref "U8") (pin "30") (pinfunction "XLAT_30") (pintype "input"))
      (node (ref "U9") (pin "7") (pinfunction "PA06/EINT6/AIN6/SERCOM0.2_7") (pintype "bidirectional"))
    )
    (net (code "15") (name "MCU_ACTIVE") (class "Default")
      (node (ref "Q3") (pin "1") (pinfunction "G_1") (pintype "passive"))
      (node (ref "U9") (pin "13") (pinfunction "PA10/I10/AIN18/SERCOM+2.2/I2SCK_13") (pintype "bidirectional"))
    )
    (net (code "16") (name "MSG_CLK") (class "Default")
      (node (ref "U4") (pin "4") (pinfunction "STROBE_4") (pintype "input"))
      (node (ref "U9") (pin "1") (pinfunction "PA00/EINT0/SERCOM1.0_1") (pintype "bidirectional"))
    )
    (net (code "17") (name "MSG_RST") (class "Default")
      (node (ref "U4") (pin "7") (pinfunction "~{RESET}_7") (pintype "input"))
      (node (ref "U9") (pin "2") (pinfunction "PA01/EINT1/SERCOM1.1_2") (pintype "bidirectional"))
    )
    (net (code "18") (name "Net-(C4-Pad2)") (class "Default")
      (node (ref "C4") (pin "2") (pinfunction "2_2") (pintype "passive"))
      (node (ref "R12") (pin "1") (pinfunction "1_1") (pintype "passive"))
      (node (ref "R13") (pin "2") (pinfunction "2_2") (pintype "passive"))
    )
    (net (code "19") (name "Net-(D1-REF)") (class "Default")
      (node (ref "D1") (pin "1") (pinfunction "REF_1") (pintype "power_in"))
      (node (ref "R14") (pin "1") (pinfunction "1_1") (pintype "passive"))
      (node (ref "R5") (pin "2") (pinfunction "2_2") (pintype "passive"))
    )
    (net (code "20") (name "Net-(D7-K)") (class "Default")
      (node (ref "C14") (pin "2") (pinfunction "2_2") (pintype "passive"))
      (node (ref "D7") (pin "2") (pinfunction "K_2") (pintype "passive"))
      (node (ref "Q1") (pin "3") (pinfunction "S_3") (pintype "passive"))
      (node (ref "Q2") (pin "3") (pinfunction "S_3") (pintype "passive"))
      (node (ref "R20") (pin "2") (pinfunction "2_2") (pintype "passive"))
    )
    (net (code "21") (name "Net-(D8-Pad1)") (class "Default")
      (node (ref "D8") (pin "1") (pinfunction "1_1") (pintype "passive"))
      (node (ref "R17") (pin "1") (pinfunction "1_1") (pintype "passive"))
    )
    (net (code "22") (name "Net-(D9-Pad1)") (class "Default")
      (node (ref "D9") (pin "1") (pinfunction "1_1") (pintype "passive"))
      (node (ref "R18") (pin "1") (pinfunction "1_1") (pintype "passive"))
    )
    (net (code "23") (name "Net-(D10-Pad1)") (class "Default")
      (node (ref "D10") (pin "1") (pinfunction "1_1") (pintype "passive"))
      (node (ref "R19") (pin "1") (pinfunction "1_1") (pintype "passive"))
    )
    (net (code "24") (name "Net-(D21-Pad2)") (class "Default")
      (node (ref "D21") (pin "2") (pinfunction "2_2") (pintype "passive"))
      (node (ref "R26") (pin "2") (pinfunction "2_2") (pintype "passive"))
    )
    (net (code "25") (name "Net-(D28-Pad2)") (class "Default")
      (node (ref "D28") (pin "2") (pinfunction "2_2") (pintype "passive"))
      (node (ref "R27") (pin "2") (pinfunction "2_2") (pintype "passive"))
    )
    (net (code "26") (name "Net-(D33-Pad2)") (class "Default")
      (node (ref "D33") (pin "2") (pinfunction "2_2") (pintype "passive"))
      (node (ref "R29") (pin "2") (pinfunction "2_2") (pintype "passive"))
    )
    (net (code "27") (name "Net-(D62-Pad1)") (class "Default")
      (node (ref "D62") (pin "1") (pinfunction "1_1") (pintype "passive"))
      (node (ref "R34") (pin "1") (pinfunction "1_1") (pintype "passive"))
    )
    (net (code "28") (name "Net-(F1-Pad2)") (class "Default")
      (node (ref "F1") (pin "2") (pinfunction "2_2") (pintype "passive"))
      (node (ref "FB1") (pin "1") (pinfunction "1_1") (pintype "passive"))
    )
    (net (code "29") (name "Net-(J1-SHLD-Pad1)") (class "Default")
      (node (ref "J1") (pin "1") (pinfunction "SHLD_1") (pintype "passive"))
      (node (ref "J1") (pin "2") (pinfunction "SHLD_2") (pintype "passive"))
      (node (ref "J1") (pin "3") (pinfunction "SHLD_3") (pintype "passive"))
      (node (ref "J1") (pin "4") (pinfunction "SHLD_4") (pintype "passive"))
      (node (ref "R16") (pin "2") (pinfunction "2_2") (pintype "passive"))
    )
    (net (code "30") (name "Net-(J2-T)") (class "Default")
      (node (ref "D6") (pin "2") (pinfunction "2_2") (pintype "passive"))
      (node (ref "J2") (pin "3") (pinfunction "T_3") (pintype "input"))
      (node (ref "R12") (pin "2") (pinfunction "2_2") (pintype "passive"))
    )
    (net (code "31") (name "Net-(Q2-G)") (class "Default")
      (node (ref "Q2") (pin "1") (pinfunction "G_1") (pintype "passive"))
      (node (ref "R20") (pin "1") (pinfunction "1_1") (pintype "passive"))
      (node (ref "S2") (pin "2") (pinfunction "2_2") (pintype "passive"))
    )
    (net (code "32") (name "Net-(Q3-D)") (class "Default")
      (node (ref "D8") (pin "2") (pinfunction "2_2") (pintype "passive"))
      (node (ref "Q3") (pin "2") (pinfunction "D_2") (pintype "passive"))
    )
    (net (code "33") (name "Net-(Q4-D)") (class "Default")
      (node (ref "Q4") (pin "2") (pinfunction "D_2") (pintype "passive"))
      (node (ref "R34") (pin "2") (pinfunction "2_2") (pintype "passive"))
    )
    (net (code "34") (name "Net-(Q5-D)") (class "Default")
      (node (ref "Q5") (pin "2") (pinfunction "D_2") (pintype "passive"))
      (node (ref "Q6") (pin "2") (pinfunction "D_2") (pintype "passive"))
    )
    (net (code "35") (name "Net-(Q5-G)") (class "Default")
      (node (ref "Q5") (pin "1") (pinfunction "G_1") (pintype "passive"))
      (node (ref "U11") (pin "4") (pinfunction "DO_4") (pintype "input"))
    )
    (net (code "36") (name "Net-(Q6-G)") (class "Default")
      (node (ref "Q6") (pin "1") (pinfunction "G_1") (pintype "passive"))
      (node (ref "U11") (pin "5") (pinfunction "CO_5") (pintype "input"))
    )
    (net (code "37") (name "Net-(U2A-+)") (class "Default")
      (node (ref "R13") (pin "1") (pinfunction "1_1") (pintype "passive"))
      (node (ref "R8") (pin "1") (pinfunction "1_1") (pintype "passive"))
      (node (ref "U2") (pin "3") (pinfunction "+_3") (pintype "passive"))
    )
    (net (code "38") (name "Net-(U2A--)") (class "Default")
      (node (ref "R2") (pin "1") (pinfunction "1_1") (pintype "passive"))
      (node (ref "R3") (pin "2") (pinfunction "2_2") (pintype "passive"))
      (node (ref "U2") (pin "2") (pinfunction "-_2") (pintype "passive"))
    )
    (net (code "39") (name "Net-(U2A-OUT)") (class "Default")
      (node (ref "R11") (pin "2") (pinfunction "2_2") (pintype "passive"))
      (node (ref "R3") (pin "1") (pinfunction "1_1") (pintype "passive"))
      (node (ref "U2") (pin "1") (pinfunction "OUT_1") (pintype "passive"))
    )
    (net (code "40") (name "Net-(U2B--)") (class "Default")
      (node (ref "R11") (pin "1") (pinfunction "1_1") (pintype "passive"))
      (node (ref "R6") (pin "2") (pinfunction "2_2") (pintype "passive"))
      (node (ref "U2") (pin "6") (pinfunction "-_6") (pintype "passive"))
    )
    (net (code "41") (name "Net-(U2B-OUT)") (class "Default")
      (node (ref "R6") (pin "1") (pinfunction "1_1") (pintype "passive"))
      (node (ref "R7") (pin "2") (pinfunction "2_2") (pintype "passive"))
      (node (ref "U2") (pin "7") (pinfunction "OUT_7") (pintype "passive"))
    )
    (net (code "42") (name "Net-(U3A--)") (class "Default")
      (node (ref "U3") (pin "1") (pinfunction "OUT_1") (pintype "passive"))
      (node (ref "U3") (pin "2") (pinfunction "-_2") (pintype "passive"))
    )
    (net (code "43") (name "Net-(U3B--)") (class "Default")
      (node (ref "C1") (pin "2") (pinfunction "2_2") (pintype "passive"))
      (node (ref "R4") (pin "1") (pinfunction "1_1") (pintype "passive"))
      (node (ref "R7") (pin "1") (pinfunction "1_1") (pintype "passive"))
      (node (ref "U3") (pin "6") (pinfunction "-_6") (pintype "passive"))
    )
    (net (code "44") (name "Net-(U4-AUDIO_IN)") (class "Default")
      (node (ref "C3") (pin "1") (pinfunction "1_1") (pintype "passive"))
      (node (ref "U4") (pin "5") (pinfunction "AUDIO_IN_5") (pintype "input"))
    )
    (net (code "45") (name "Net-(U4-CKIN)") (class "Default")
      (node (ref "C5") (pin "1") (pinfunction "1_1") (pintype "passive"))
      (node (ref "R15") (pin "1") (pinfunction "1_1") (pintype "passive"))
      (node (ref "U4") (pin "8") (pinfunction "CKIN_8") (pintype "passive"))
    )
    (net (code "46") (name "Net-(U4-GNDREF)") (class "Default")
      (node (ref "C6") (pin "1") (pinfunction "1_1") (pintype "passive"))
      (node (ref "U4") (pin "6") (pinfunction "GNDREF_6") (pintype "power_in"))
    )
    (net (code "47") (name "Net-(U7-IREF)") (class "Default")
      (node (ref "R32") (pin "2") (pinfunction "2_2") (pintype "passive"))
      (node (ref "U7") (pin "31") (pinfunction "IREF_31") (pintype "input"))
    )
    (net (code "48") (name "Net-(U7-OUT0)") (class "Default")
      (node (ref "D11") (pin "2") (pinfunction "2_2") (pintype "passive"))
      (node (ref "U7") (pin "5") (pinfunction "OUT0_5") (pintype "input"))
    )
    (net (code "49") (name "Net-(U7-OUT1)") (class "Default")
      (node (ref "D13") (pin "2") (pinfunction "2_2") (pintype "passive"))
      (node (ref "U7") (pin "6") (pinfunction "OUT1_6") (pintype "input"))
    )
    (net (code "50") (name "Net-(U7-OUT2)") (class "Default")
      (node (ref "D15") (pin "2") (pinfunction "2_2") (pintype "passive"))
      (node (ref "U7") (pin "7") (pinfunction "OUT2_7") (pintype "input"))
    )
    (net (code "51") (name "Net-(U7-OUT3)") (class "Default")
      (node (ref "D17") (pin "2") (pinfunction "2_2") (pintype "passive"))
      (node (ref "U7") (pin "8") (pinfunction "OUT3_8") (pintype "input"))
    )
    (net (code "52") (name "Net-(U7-OUT4)") (class "Default")
      (node (ref "D19") (pin "2") (pinfunction "2_2") (pintype "passive"))
      (node (ref "U7") (pin "9") (pinfunction "OUT4_9") (pintype "input"))
    )
    (net (code "53") (name "Net-(U7-OUT5)") (class "Default")
      (node (ref "D22") (pin "2") (pinfunction "2_2") (pintype "passive"))
      (node (ref "U7") (pin "10") (pinfunction "OUT5_10") (pintype "input"))
    )
    (net (code "54") (name "Net-(U7-OUT6)") (class "Default")
      (node (ref "D24") (pin "2") (pinfunction "2_2") (pintype "passive"))
      (node (ref "U7") (pin "11") (pinfunction "OUT6_11") (pintype "input"))
    )
    (net (code "55") (name "Net-(U7-OUT7)") (class "Default")
      (node (ref "D26") (pin "2") (pinfunction "2_2") (pintype "passive"))
      (node (ref "U7") (pin "12") (pinfunction "OUT7_12") (pintype "input"))
    )
    (net (code "56") (name "Net-(U7-OUT8)") (class "Default")
      (node (ref "D29") (pin "2") (pinfunction "2_2") (pintype "passive"))
      (node (ref "U7") (pin "13") (pinfunction "OUT8_13") (pintype "input"))
    )
    (net (code "57") (name "Net-(U7-OUT9)") (class "Default")
      (node (ref "D31") (pin "2") (pinfunction "2_2") (pintype "passive"))
      (node (ref "U7") (pin "14") (pinfunction "OUT9_14") (pintype "input"))
    )
    (net (code "58") (name "Net-(U7-OUT10)") (class "Default")
      (node (ref "D34") (pin "2") (pinfunction "2_2") (pintype "passive"))
      (node (ref "U7") (pin "15") (pinfunction "OUT10_15") (pintype "input"))
    )
    (net (code "59") (name "Net-(U7-OUT11)") (class "Default")
      (node (ref "D36") (pin "2") (pinfunction "2_2") (pintype "passive"))
      (node (ref "U7") (pin "16") (pinfunction "OUT11_16") (pintype "input"))
    )
    (net (code "60") (name "Net-(U7-OUT12)") (class "Default")
      (node (ref "D38") (pin "2") (pinfunction "2_2") (pintype "passive"))
      (node (ref "U7") (pin "17") (pinfunction "OUT12_17") (pintype "input"))
    )
    (net (code "61") (name "Net-(U7-OUT13)") (class "Default")
      (node (ref "D40") (pin "2") (pinfunction "2_2") (pintype "passive"))
      (node (ref "U7") (pin "18") (pinfunction "OUT13_18") (pintype "input"))
    )
    (net (code "62") (name "Net-(U7-OUT14)") (class "Default")
      (node (ref "D42") (pin "2") (pinfunction "2_2") (pintype "passive"))
      (node (ref "U7") (pin "19") (pinfunction "OUT14_19") (pintype "input"))
    )
    (net (code "63") (name "Net-(U7-OUT15)") (class "Default")
      (node (ref "D44") (pin "2") (pinfunction "2_2") (pintype "passive"))
      (node (ref "U7") (pin "20") (pinfunction "OUT15_20") (pintype "input"))
    )
    (net (code "64") (name "Net-(U7-OUT16)") (class "Default")
      (node (ref "D46") (pin "2") (pinfunction "2_2") (pintype "passive"))
      (node (ref "U7") (pin "21") (pinfunction "OUT16_21") (pintype "input"))
    )
    (net (code "65") (name "Net-(U7-OUT17)") (class "Default")
      (node (ref "D48") (pin "2") (pinfunction "2_2") (pintype "passive"))
      (node (ref "U7") (pin "22") (pinfunction "OUT17_22") (pintype "input"))
    )
    (net (code "66") (name "Net-(U7-OUT18)") (class "Default")
      (node (ref "D50") (pin "2") (pinfunction "2_2") (pintype "passive"))
      (node (ref "U7") (pin "23") (pinfunction "OUT18_23") (pintype "input"))
    )
    (net (code "67") (name "Net-(U7-OUT19)") (class "Default")
      (node (ref "D52") (pin "2") (pinfunction "2_2") (pintype "passive"))
      (node (ref "U7") (pin "24") (pinfunction "OUT19_24") (pintype "input"))
    )
    (net (code "68") (name "Net-(U7-OUT20)") (class "Default")
      (node (ref "D54") (pin "2") (pinfunction "2_2") (pintype "passive"))
      (node (ref "U7") (pin "25") (pinfunction "OUT20_25") (pintype "input"))
    )
    (net (code "69") (name "Net-(U7-OUT21)") (class "Default")
      (node (ref "D56") (pin "2") (pinfunction "2_2") (pintype "passive"))
      (node (ref "U7") (pin "26") (pinfunction "OUT21_26") (pintype "input"))
    )
    (net (code "70") (name "Net-(U7-OUT22)") (class "Default")
      (node (ref "D58") (pin "2") (pinfunction "2_2") (pintype "passive"))
      (node (ref "U7") (pin "27") (pinfunction "OUT22_27") (pintype "input"))
    )
    (net (code "71") (name "Net-(U7-OUT23)") (class "Default")
      (node (ref "D60") (pin "2") (pinfunction "2_2") (pintype "passive"))
      (node (ref "U7") (pin "28") (pinfunction "OUT23_28") (pintype "input"))
    )
    (net (code "72") (name "Net-(U8-IREF)") (class "Default")
      (node (ref "R33") (pin "2") (pinfunction "2_2") (pintype "passive"))
      (node (ref "U8") (pin "31") (pinfunction "IREF_31") (pintype "input"))
    )
    (net (code "73") (name "Net-(U8-OUT0)") (class "Default")
      (node (ref "D12") (pin "2") (pinfunction "2_2") (pintype "passive"))
      (node (ref "U8") (pin "5") (pinfunction "OUT0_5") (pintype "input"))
    )
    (net (code "74") (name "Net-(U8-OUT1)") (class "Default")
      (node (ref "D14") (pin "2") (pinfunction "2_2") (pintype "passive"))
      (node (ref "U8") (pin "6") (pinfunction "OUT1_6") (pintype "input"))
    )
    (net (code "75") (name "Net-(U8-OUT2)") (class "Default")
      (node (ref "D16") (pin "2") (pinfunction "2_2") (pintype "passive"))
      (node (ref "U8") (pin "7") (pinfunction "OUT2_7") (pintype "input"))
    )
    (net (code "76") (name "Net-(U8-OUT3)") (class "Default")
      (node (ref "D18") (pin "2") (pinfunction "2_2") (pintype "passive"))
      (node (ref "U8") (pin "8") (pinfunction "OUT3_8") (pintype "input"))
    )
    (net (code "77") (name "Net-(U8-OUT4)") (class "Default")
      (node (ref "D20") (pin "2") (pinfunction "2_2") (pintype "passive"))
      (node (ref "U8") (pin "9") (pinfunction "OUT4_9") (pintype "input"))
    )
    (net (code "78") (name "Net-(U8-OUT5)") (class "Default")
      (node (ref "D23") (pin "2") (pinfunction "2_2") (pintype "passive"))
      (node (ref "U8") (pin "10") (pinfunction "OUT5_10") (pintype "input"))
    )
    (net (code "79") (name "Net-(U8-OUT6)") (class "Default")
      (node (ref "D25") (pin "2") (pinfunction "2_2") (pintype "passive"))
      (node (ref "U8") (pin "11") (pinfunction "OUT6_11") (pintype "input"))
    )
    (net (code "80") (name "Net-(U8-OUT7)") (class "Default")
      (node (ref "D27") (pin "2") (pinfunction "2_2") (pintype "passive"))
      (node (ref "U8") (pin "12") (pinfunction "OUT7_12") (pintype "input"))
    )
    (net (code "81") (name "Net-(U8-OUT8)") (class "Default")
      (node (ref "D30") (pin "2") (pinfunction "2_2") (pintype "passive"))
      (node (ref "U8") (pin "13") (pinfunction "OUT8_13") (pintype "input"))
    )
    (net (code "82") (name "Net-(U8-OUT9)") (class "Default")
      (node (ref "D32") (pin "2") (pinfunction "2_2") (pintype "passive"))
      (node (ref "U8") (pin "14") (pinfunction "OUT9_14") (pintype "input"))
    )
    (net (code "83") (name "Net-(U8-OUT10)") (class "Default")
      (node (ref "D35") (pin "2") (pinfunction "2_2") (pintype "passive"))
      (node (ref "U8") (pin "15") (pinfunction "OUT10_15") (pintype "input"))
    )
    (net (code "84") (name "Net-(U8-OUT11)") (class "Default")
      (node (ref "D37") (pin "2") (pinfunction "2_2") (pintype "passive"))
      (node (ref "U8") (pin "16") (pinfunction "OUT11_16") (pintype "input"))
    )
    (net (code "85") (name "Net-(U8-OUT12)") (class "Default")
      (node (ref "D39") (pin "2") (pinfunction "2_2") (pintype "passive"))
      (node (ref "U8") (pin "17") (pinfunction "OUT12_17") (pintype "input"))
    )
    (net (code "86") (name "Net-(U8-OUT13)") (class "Default")
      (node (ref "D41") (pin "2") (pinfunction "2_2") (pintype "passive"))
      (node (ref "U8") (pin "18") (pinfunction "OUT13_18") (pintype "input"))
    )
    (net (code "87") (name "Net-(U8-OUT14)") (class "Default")
      (node (ref "D43") (pin "2") (pinfunction "2_2") (pintype "passive"))
      (node (ref "U8") (pin "19") (pinfunction "OUT14_19") (pintype "input"))
    )
    (net (code "88") (name "Net-(U8-OUT15)") (class "Default")
      (node (ref "D45") (pin "2") (pinfunction "2_2") (pintype "passive"))
      (node (ref "U8") (pin "20") (pinfunction "OUT15_20") (pintype "input"))
    )
    (net (code "89") (name "Net-(U8-OUT16)") (class "Default")
      (node (ref "D47") (pin "2") (pinfunction "2_2") (pintype "passive"))
      (node (ref "U8") (pin "21") (pinfunction "OUT16_21") (pintype "input"))
    )
    (net (code "90") (name "Net-(U8-OUT17)") (class "Default")
      (node (ref "D49") (pin "2") (pinfunction "2_2") (pintype "passive"))
      (node (ref "U8") (pin "22") (pinfunction "OUT17_22") (pintype "input"))
    )
    (net (code "91") (name "Net-(U8-OUT18)") (class "Default")
      (node (ref "D51") (pin "2") (pinfunction "2_2") (pintype "passive"))
      (node (ref "U8") (pin "23") (pinfunction "OUT18_23") (pintype "input"))
    )
    (net (code "92") (name "Net-(U8-OUT19)") (class "Default")
      (node (ref "D53") (pin "2") (pinfunction "2_2") (pintype "passive"))
      (node (ref "U8") (pin "24") (pinfunction "OUT19_24") (pintype "input"))
    )
    (net (code "93") (name "Net-(U8-OUT20)") (class "Default")
      (node (ref "D55") (pin "2") (pinfunction "2_2") (pintype "passive"))
      (node (ref "U8") (pin "25") (pinfunction "OUT20_25") (pintype "input"))
    )
    (net (code "94") (name "Net-(U8-OUT21)") (class "Default")
      (node (ref "D57") (pin "2") (pinfunction "2_2") (pintype "passive"))
      (node (ref "U8") (pin "26") (pinfunction "OUT21_26") (pintype "input"))
    )
    (net (code "95") (name "Net-(U8-OUT22)") (class "Default")
      (node (ref "D59") (pin "2") (pinfunction "2_2") (pintype "passive"))
      (node (ref "U8") (pin "27") (pinfunction "OUT22_27") (pintype "input"))
    )
    (net (code "96") (name "Net-(U8-OUT23)") (class "Default")
      (node (ref "D61") (pin "2") (pinfunction "2_2") (pintype "passive"))
      (node (ref "U8") (pin "28") (pinfunction "OUT23_28") (pintype "input"))
    )
    (net (code "97") (name "Net-(U9-VDDCORE)") (class "Default")
      (node (ref "C32") (pin "2") (pinfunction "2_2") (pintype "passive"))
      (node (ref "U9") (pin "29") (pinfunction "VDDCORE_29") (pintype "power_in"))
    )
    (net (code "98") (name "Net-(U10-PROG)") (class "Default")
      (node (ref "R30") (pin "1") (pinfunction "1_1") (pintype "passive"))
      (node (ref "U10") (pin "6") (pinfunction "PROG_6") (pintype "output"))
    )
    (net (code "99") (name "Net-(U10-STAT1)") (class "Default")
      (node (ref "R26") (pin "1") (pinfunction "1_1") (pintype "passive"))
      (node (ref "U10") (pin "3") (pinfunction "STAT1_3") (pintype "input"))
    )
    (net (code "100") (name "Net-(U10-STAT2)") (class "Default")
      (node (ref "R27") (pin "1") (pinfunction "1_1") (pintype "passive"))
      (node (ref "U10") (pin "4") (pinfunction "STAT2_4") (pintype "input"))
    )
    (net (code "101") (name "Net-(U10-THERM)") (class "Default")
      (node (ref "R28") (pin "1") (pinfunction "1_1") (pintype "passive"))
      (node (ref "U10") (pin "8") (pinfunction "THERM_8") (pintype "input"))
    )
    (net (code "102") (name "Net-(U10-~{PG})") (class "Default")
      (node (ref "R29") (pin "1") (pinfunction "1_1") (pintype "passive"))
      (node (ref "U10") (pin "7") (pinfunction "~{PG}_7") (pintype "input"))
    )
    (net (code "103") (name "Net-(U11-VDD)") (class "Default")
      (node (ref "C33") (pin "2") (pinfunction "2_2") (pintype "passive"))
      (node (ref "R31") (pin "1") (pinfunction "1_1") (pintype "passive"))
      (node (ref "U11") (pin "2") (pinfunction "VDD_2") (pintype "input"))
    )
    (net (code "104") (name "Net-(U11-VM)") (class "Default")
      (node (ref "R35") (pin "1") (pinfunction "1_1") (pintype "passive"))
      (node (ref "U11") (pin "1") (pinfunction "VM_1") (pintype "input"))
    )
    (net (code "105") (name "RESET") (class "Default")
      (node (ref "C20") (pin "2") (pinfunction "2_2") (pintype "passive"))
      (node (ref "R25") (pin "1") (pinfunction "1_1") (pintype "passive"))
      (node (ref "U9") (pin "26") (pinfunction "/RESET_26") (pintype "input"))
    )
    (net (code "106") (name "RST_IN") (class "Default")
      (node (ref "Q4") (pin "1") (pinfunction "G_1") (pintype "passive"))
      (node (ref "R25") (pin "2") (pinfunction "2_2") (pintype "passive"))
      (node (ref "S1") (pin "2") (pinfunction "2_2") (pintype "passive"))
      (node (ref "U12") (pin "1") (pinfunction "VOUT_1") (pintype "passive"))
    )
    (net (code "107") (name "SER_D0") (class "Default")
      (node (ref "U7") (pin "4") (pinfunction "SIN_4") (pintype "input"))
      (node (ref "U9") (pin "12") (pinfunction "PA09/I2C/I9/AIN17/SERCOM+2.1/I2SMC_12") (pintype "bidirectional"))
    )
    (net (code "108") (name "SER_D1") (class "Default")
      (node (ref "U7") (pin "29") (pinfunction "SOUT_29") (pintype "input"))
      (node (ref "U8") (pin "4") (pinfunction "SIN_4") (pintype "input"))
    )
    (net (code "109") (name "SWCLK") (class "Default")
      (node (ref "U9") (pin "31") (pinfunction "PA30/I10/SECOM1.2/SWCLK_31") (pintype "bidirectional"))
    )
    (net (code "110") (name "SWDIO") (class "Default")
      (node (ref "U9") (pin "32") (pinfunction "PA31/I11/SECOM1.3/SWDIO_32") (pintype "bidirectional"))
    )
    (net (code "111") (name "USB_D_MINUS") (class "Default")
      (node (ref "J1") (pin "A7") (pinfunction "D-_A7") (pintype "passive"))
      (node (ref "J1") (pin "B7") (pinfunction "D-_B7") (pintype "passive"))
      (node (ref "U1") (pin "1") (pinfunction "I/O1_1") (pintype "passive"))
    )
    (net (code "112") (name "USB_D_PLUS") (class "Default")
      (node (ref "J1") (pin "A6") (pinfunction "D+_A6") (pintype "passive"))
      (node (ref "J1") (pin "B6") (pinfunction "D+_B6") (pintype "passive"))
      (node (ref "U1") (pin "3") (pinfunction "I/O2_3") (pintype "passive"))
    )
    (net (code "113") (name "USB_VDD") (class "Default")
      (node (ref "D5") (pin "2") (pinfunction "2_2") (pintype "passive"))
      (node (ref "F1") (pin "1") (pinfunction "1_1") (pintype "passive"))
      (node (ref "J1") (pin "A4_B9") (pinfunction "VBUS_A4_B9") (pintype "passive"))
      (node (ref "J1") (pin "B4_A9") (pinfunction "VBUS_B4_A9") (pintype "passive"))
      (node (ref "U1") (pin "5") (pinfunction "VBUS_5") (pintype "passive"))
    )
    (net (code "114") (name "VBAT") (class "Default")
      (node (ref "C27") (pin "2") (pinfunction "2_2") (pintype "passive"))
      (node (ref "J3") (pin "1") (pinfunction "1_1") (pintype "passive"))
      (node (ref "Q1") (pin "2") (pinfunction "D_2") (pintype "passive"))
      (node (ref "Q4") (pin "3") (pinfunction "S_3") (pintype "passive"))
      (node (ref "R31") (pin "2") (pinfunction "2_2") (pintype "passive"))
      (node (ref "U10") (pin "10") (pinfunction "VBAT_10") (pintype "power_in"))
      (node (ref "U10") (pin "9") (pinfunction "VBAT_9") (pintype "power_in"))
      (node (ref "U12") (pin "3") (pinfunction "VIN_3") (pintype "power_in"))
    )
    (net (code "115") (name "VBUS") (class "Default")
      (node (ref "C28") (pin "2") (pinfunction "2_2") (pintype "passive"))
      (node (ref "D21") (pin "1") (pinfunction "1_1") (pintype "passive"))
      (node (ref "D28") (pin "1") (pinfunction "1_1") (pintype "passive"))
      (node (ref "D33") (pin "1") (pinfunction "1_1") (pintype "passive"))
      (node (ref "D7") (pin "1") (pinfunction "A_1") (pintype "passive"))
      (node (ref "FB1") (pin "2") (pinfunction "2_2") (pintype "passive"))
      (node (ref "Q1") (pin "1") (pinfunction "G_1") (pintype "passive"))
      (node (ref "R21") (pin "2") (pinfunction "2_2") (pintype "passive"))
      (node (ref "U10") (pin "1") (pinfunction "VDD_1") (pintype "power_in"))
      (node (ref "U10") (pin "2") (pinfunction "VDD_2") (pintype "power_in"))
    )
    (net (code "116") (name "V_REF") (class "Default")
      (node (ref "D1") (pin "2") (pinfunction "K_2") (pintype "passive"))
      (node (ref "R1") (pin "2") (pinfunction "2_2") (pintype "passive"))
      (node (ref "R5") (pin "1") (pinfunction "1_1") (pintype "passive"))
      (node (ref "R8") (pin "2") (pinfunction "2_2") (pintype "passive"))
      (node (ref "U2") (pin "5") (pinfunction "+_5") (pintype "passive"))
      (node (ref "U3") (pin "3") (pinfunction "+_3") (pintype "passive"))
      (node (ref "U3") (pin "5") (pinfunction "+_5") (pintype "passive"))
    )
    (net (code "117") (name "V_UNREG") (class "Default")
      (node (ref "C12") (pin "2") (pinfunction "2_2") (pintype "passive"))
      (node (ref "C18") (pin "2") (pinfunction "2_2") (pintype "passive"))
      (node (ref "C22") (pin "2") (pinfunction "2_2") (pintype "passive"))
      (node (ref "C23") (pin "2") (pinfunction "2_2") (pintype "passive"))
      (node (ref "C25") (pin "2") (pinfunction "2_2") (pintype "passive"))
      (node (ref "C26") (pin "2") (pinfunction "2_2") (pintype "passive"))
      (node (ref "D11") (pin "1") (pinfunction "1_1") (pintype "passive"))
      (node (ref "D12") (pin "1") (pinfunction "1_1") (pintype "passive"))
      (node (ref "D13") (pin "1") (pinfunction "1_1") (pintype "passive"))
      (node (ref "D14") (pin "1") (pinfunction "1_1") (pintype "passive"))
      (node (ref "D15") (pin "1") (pinfunction "1_1") (pintype "passive"))
      (node (ref "D16") (pin "1") (pinfunction "1_1") (pintype "passive"))
      (node (ref "D17") (pin "1") (pinfunction "1_1") (pintype "passive"))
      (node (ref "D18") (pin "1") (pinfunction "1_1") (pintype "passive"))
      (node (ref "D19") (pin "1") (pinfunction "1_1") (pintype "passive"))
      (node (ref "D20") (pin "1") (pinfunction "1_1") (pintype "passive"))
      (node (ref "D22") (pin "1") (pinfunction "1_1") (pintype "passive"))
      (node (ref "D23") (pin "1") (pinfunction "1_1") (pintype "passive"))
      (node (ref "D24") (pin "1") (pinfunction "1_1") (pintype "passive"))
      (node (ref "D25") (pin "1") (pinfunction "1_1") (pintype "passive"))
      (node (ref "D26") (pin "1") (pinfunction "1_1") (pintype "passive"))
      (node (ref "D27") (pin "1") (pinfunction "1_1") (pintype "passive"))
      (node (ref "D29") (pin "1") (pinfunction "1_1") (pintype "passive"))
      (node (ref "D30") (pin "1") (pinfunction "1_1") (pintype "passive"))
      (node (ref "D31") (pin "1") (pinfunction "1_1") (pintype "passive"))
      (node (ref "D32") (pin "1") (pinfunction "1_1") (pintype "passive"))
      (node (ref "D34") (pin "1") (pinfunction "1_1") (pintype "passive"))
      (node (ref "D35") (pin "1") (pinfunction "1_1") (pintype "passive"))
      (node (ref "D36") (pin "1") (pinfunction "1_1") (pintype "passive"))
      (node (ref "D37") (pin "1") (pinfunction "1_1") (pintype "passive"))
      (node (ref "D38") (pin "1") (pinfunction "1_1") (pintype "passive"))
      (node (ref "D39") (pin "1") (pinfunction "1_1") (pintype "passive"))
      (node (ref "D4") (pin "2") (pinfunction "2_2") (pintype "passive"))
      (node (ref "D40") (pin "1") (pinfunction "1_1") (pintype "passive"))
      (node (ref "D41") (pin "1") (pinfunction "1_1") (pintype "passive"))
      (node (ref "D42") (pin "1") (pinfunction "1_1") (pintype "passive"))
      (node (ref "D43") (pin "1") (pinfunction "1_1") (pintype "passive"))
      (node (ref "D44") (pin "1") (pinfunction "1_1") (pintype "passive"))
      (node (ref "D45") (pin "1") (pinfunction "1_1") (pintype "passive"))
      (node (ref "D46") (pin "1") (pinfunction "1_1") (pintype "passive"))
      (node (ref "D47") (pin "1") (pinfunction "1_1") (pintype "passive"))
      (node (ref "D48") (pin "1") (pinfunction "1_1") (pintype "passive"))
      (node (ref "D49") (pin "1") (pinfunction "1_1") (pintype "passive"))
      (node (ref "D50") (pin "1") (pinfunction "1_1") (pintype "passive"))
      (node (ref "D51") (pin "1") (pinfunction "1_1") (pintype "passive"))
      (node (ref "D52") (pin "1") (pinfunction "1_1") (pintype "passive"))
      (node (ref "D53") (pin "1") (pinfunction "1_1") (pintype "passive"))
      (node (ref "D54") (pin "1") (pinfunction "1_1") (pintype "passive"))
      (node (ref "D55") (pin "1") (pinfunction "1_1") (pintype "passive"))
      (node (ref "D56") (pin "1") (pinfunction "1_1") (pintype "passive"))
      (node (ref "D57") (pin "1") (pinfunction "1_1") (pintype "passive"))
      (node (ref "D58") (pin "1") (pinfunction "1_1") (pintype "passive"))
      (node (ref "D59") (pin "1") (pinfunction "1_1") (pintype "passive"))
      (node (ref "D60") (pin "1") (pinfunction "1_1") (pintype "passive"))
      (node (ref "D61") (pin "1") (pinfunction "1_1") (pintype "passive"))
      (node (ref "Q2") (pin "2") (pinfunction "D_2") (pintype "passive"))
      (node (ref "R22") (pin "2") (pinfunction "2_2") (pintype "passive"))
      (node (ref "U5") (pin "1") (pinfunction "VIN_1") (pintype "passive"))
      (node (ref "U5") (pin "3") (pinfunction "EN_3") (pintype "passive"))
      (node (ref "U6") (pin "1") (pinfunction "VIN_1") (pintype "passive"))
      (node (ref "U6") (pin "3") (pinfunction "EN_3") (pintype "passive"))
    )
    (net (code "118") (name "unconnected-(J2-R-Pad2)") (class "Default")
      (node (ref "J2") (pin "2") (pinfunction "R_2") (pintype "input+no_connect"))
    )
    (net (code "119") (name "unconnected-(S2-Pad3)") (class "Default")
      (node (ref "S2") (pin "3") (pinfunction "3_3") (pintype "passive+no_connect"))
    )
    (net (code "120") (name "unconnected-(U8-SOUT-Pad29)") (class "Default")
      (node (ref "U8") (pin "29") (pinfunction "SOUT_29") (pintype "input+no_connect"))
    )
    (net (code "121") (name "unconnected-(U9-PA03{slash}EINT3{slash}VREFA{slash}AIN1-Pad4)") (class "Default")
      (node (ref "U9") (pin "4") (pinfunction "PA03/EINT3/VREFA/AIN1_4") (pintype "bidirectional+no_connect"))
    )
    (net (code "122") (name "unconnected-(U9-PA04{slash}EINT4{slash}VREFB{slash}AIN4{slash}SERCOM0.0-Pad5)") (class "Default")
      (node (ref "U9") (pin "5") (pinfunction "PA04/EINT4/VREFB/AIN4/SERCOM0.0_5") (pintype "bidirectional+no_connect"))
    )
    (net (code "123") (name "unconnected-(U9-PA05{slash}EINT5{slash}AIN5{slash}SERCOM0.1-Pad6)") (class "Default")
      (node (ref "U9") (pin "6") (pinfunction "PA05/EINT5/AIN5/SERCOM0.1_6") (pintype "bidirectional+no_connect"))
    )
    (net (code "124") (name "unconnected-(U9-PA11{slash}I11{slash}AIN19{slash}SERCOM0+2.3{slash}I2SF0-Pad14)") (class "Default")
      (node (ref "U9") (pin "14") (pinfunction "PA11/I11/AIN19/SERCOM0+2.3/I2SF0_14") (pintype "bidirectional+no_connect"))
    )
    (net (code "125") (name "unconnected-(U9-PA14{slash}I14{slash}SERCOM2+4.2-Pad15)") (class "Default")
      (node (ref "U9") (pin "15") (pinfunction "PA14/I14/SERCOM2+4.2_15") (pintype "bidirectional+no_connect"))
    )
    (net (code "126") (name "unconnected-(U9-PA15{slash}I15{slash}SERCOM3+4.3-Pad16)") (class "Default")
      (node (ref "U9") (pin "16") (pinfunction "PA15/I15/SERCOM3+4.3_16") (pintype "bidirectional+no_connect"))
    )
    (net (code "127") (name "unconnected-(U9-PA16{slash}I2C{slash}I0{slash}SERCOM1+3.0-Pad17)") (class "Default")
      (node (ref "U9") (pin "17") (pinfunction "PA16/I2C/I0/SERCOM1+3.0_17") (pintype "bidirectional+no_connect"))
    )
    (net (code "128") (name "unconnected-(U9-PA17{slash}I2C{slash}I1{slash}SERCOM1+3.1-Pad18)") (class "Default")
      (node (ref "U9") (pin "18") (pinfunction "PA17/I2C/I1/SERCOM1+3.1_18") (pintype "bidirectional+no_connect"))
    )
    (net (code "129") (name "unconnected-(U9-PA18{slash}I2{slash}SERCOM1+3.2-Pad19)") (class "Default")
      (node (ref "U9") (pin "19") (pinfunction "PA18/I2/SERCOM1+3.2_19") (pintype "bidirectional+no_connect"))
    )
    (net (code "130") (name "unconnected-(U9-PA19{slash}I3{slash}I0{slash}SERCOM1+3.3{slash}I2SD0-Pad20)") (class "Default")
      (node (ref "U9") (pin "20") (pinfunction "PA19/I3/I0/SERCOM1+3.3/I2SD0_20") (pintype "bidirectional+no_connect"))
    )
    (net (code "131") (name "unconnected-(U9-PA22{slash}I2C{slash}I6{slash}SERCOM3+5.0-Pad21)") (class "Default")
      (node (ref "U9") (pin "21") (pinfunction "PA22/I2C/I6/SERCOM3+5.0_21") (pintype "bidirectional+no_connect"))
    )
    (net (code "132") (name "unconnected-(U9-PA23{slash}I2C{slash}I7{slash}SERCOM3+5.1{slash}SOF-Pad22)") (class "Default")
      (node (ref "U9") (pin "22") (pinfunction "PA23/I2C/I7/SERCOM3+5.1/SOF_22") (pintype "bidirectional+no_connect"))
    )
    (net (code "133") (name "unconnected-(U9-PA27{slash}I15-Pad25)") (class "Default")
      (node (ref "U9") (pin "25") (pinfunction "PA27/I15_25") (pintype "bidirectional+no_connect"))
    )
    (net (code "134") (name "unconnected-(U9-PA28{slash}I8-Pad27)") (class "Default")
      (node (ref "U9") (pin "27") (pinfunction "PA28/I8_27") (pintype "bidirectional+no_connect"))
    )
  )
)
